# Main.net
KiCad netlist of a schematic drawn in Altium Designer
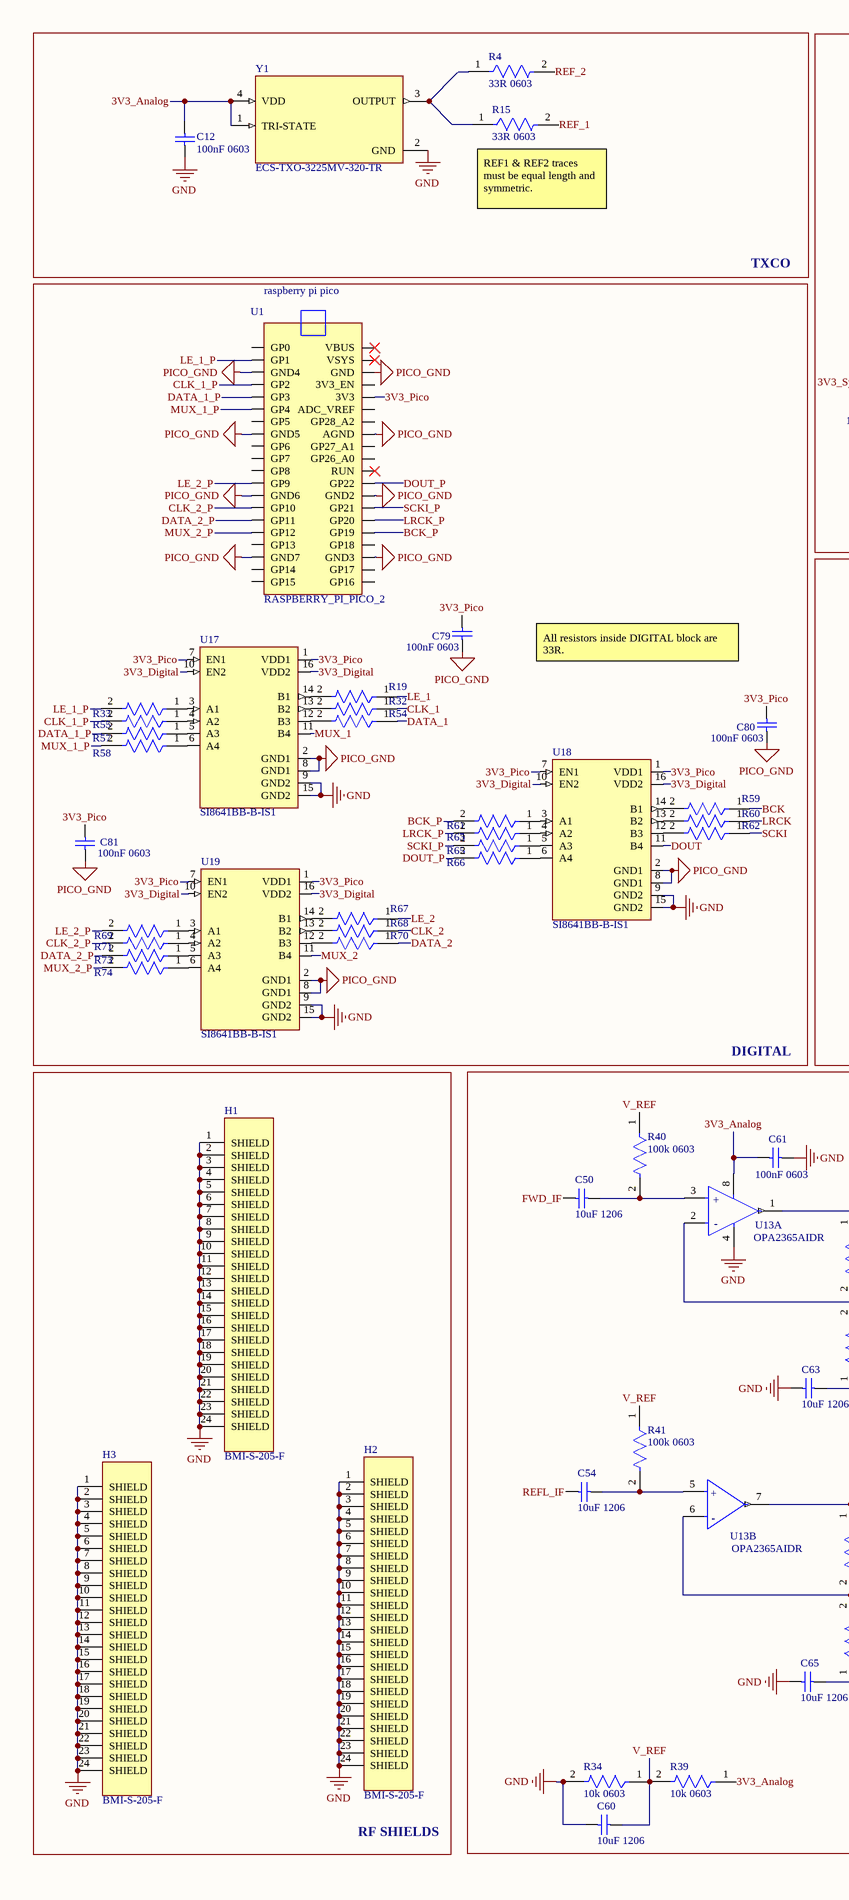
[diagram p0: Main.SchDoc, left]
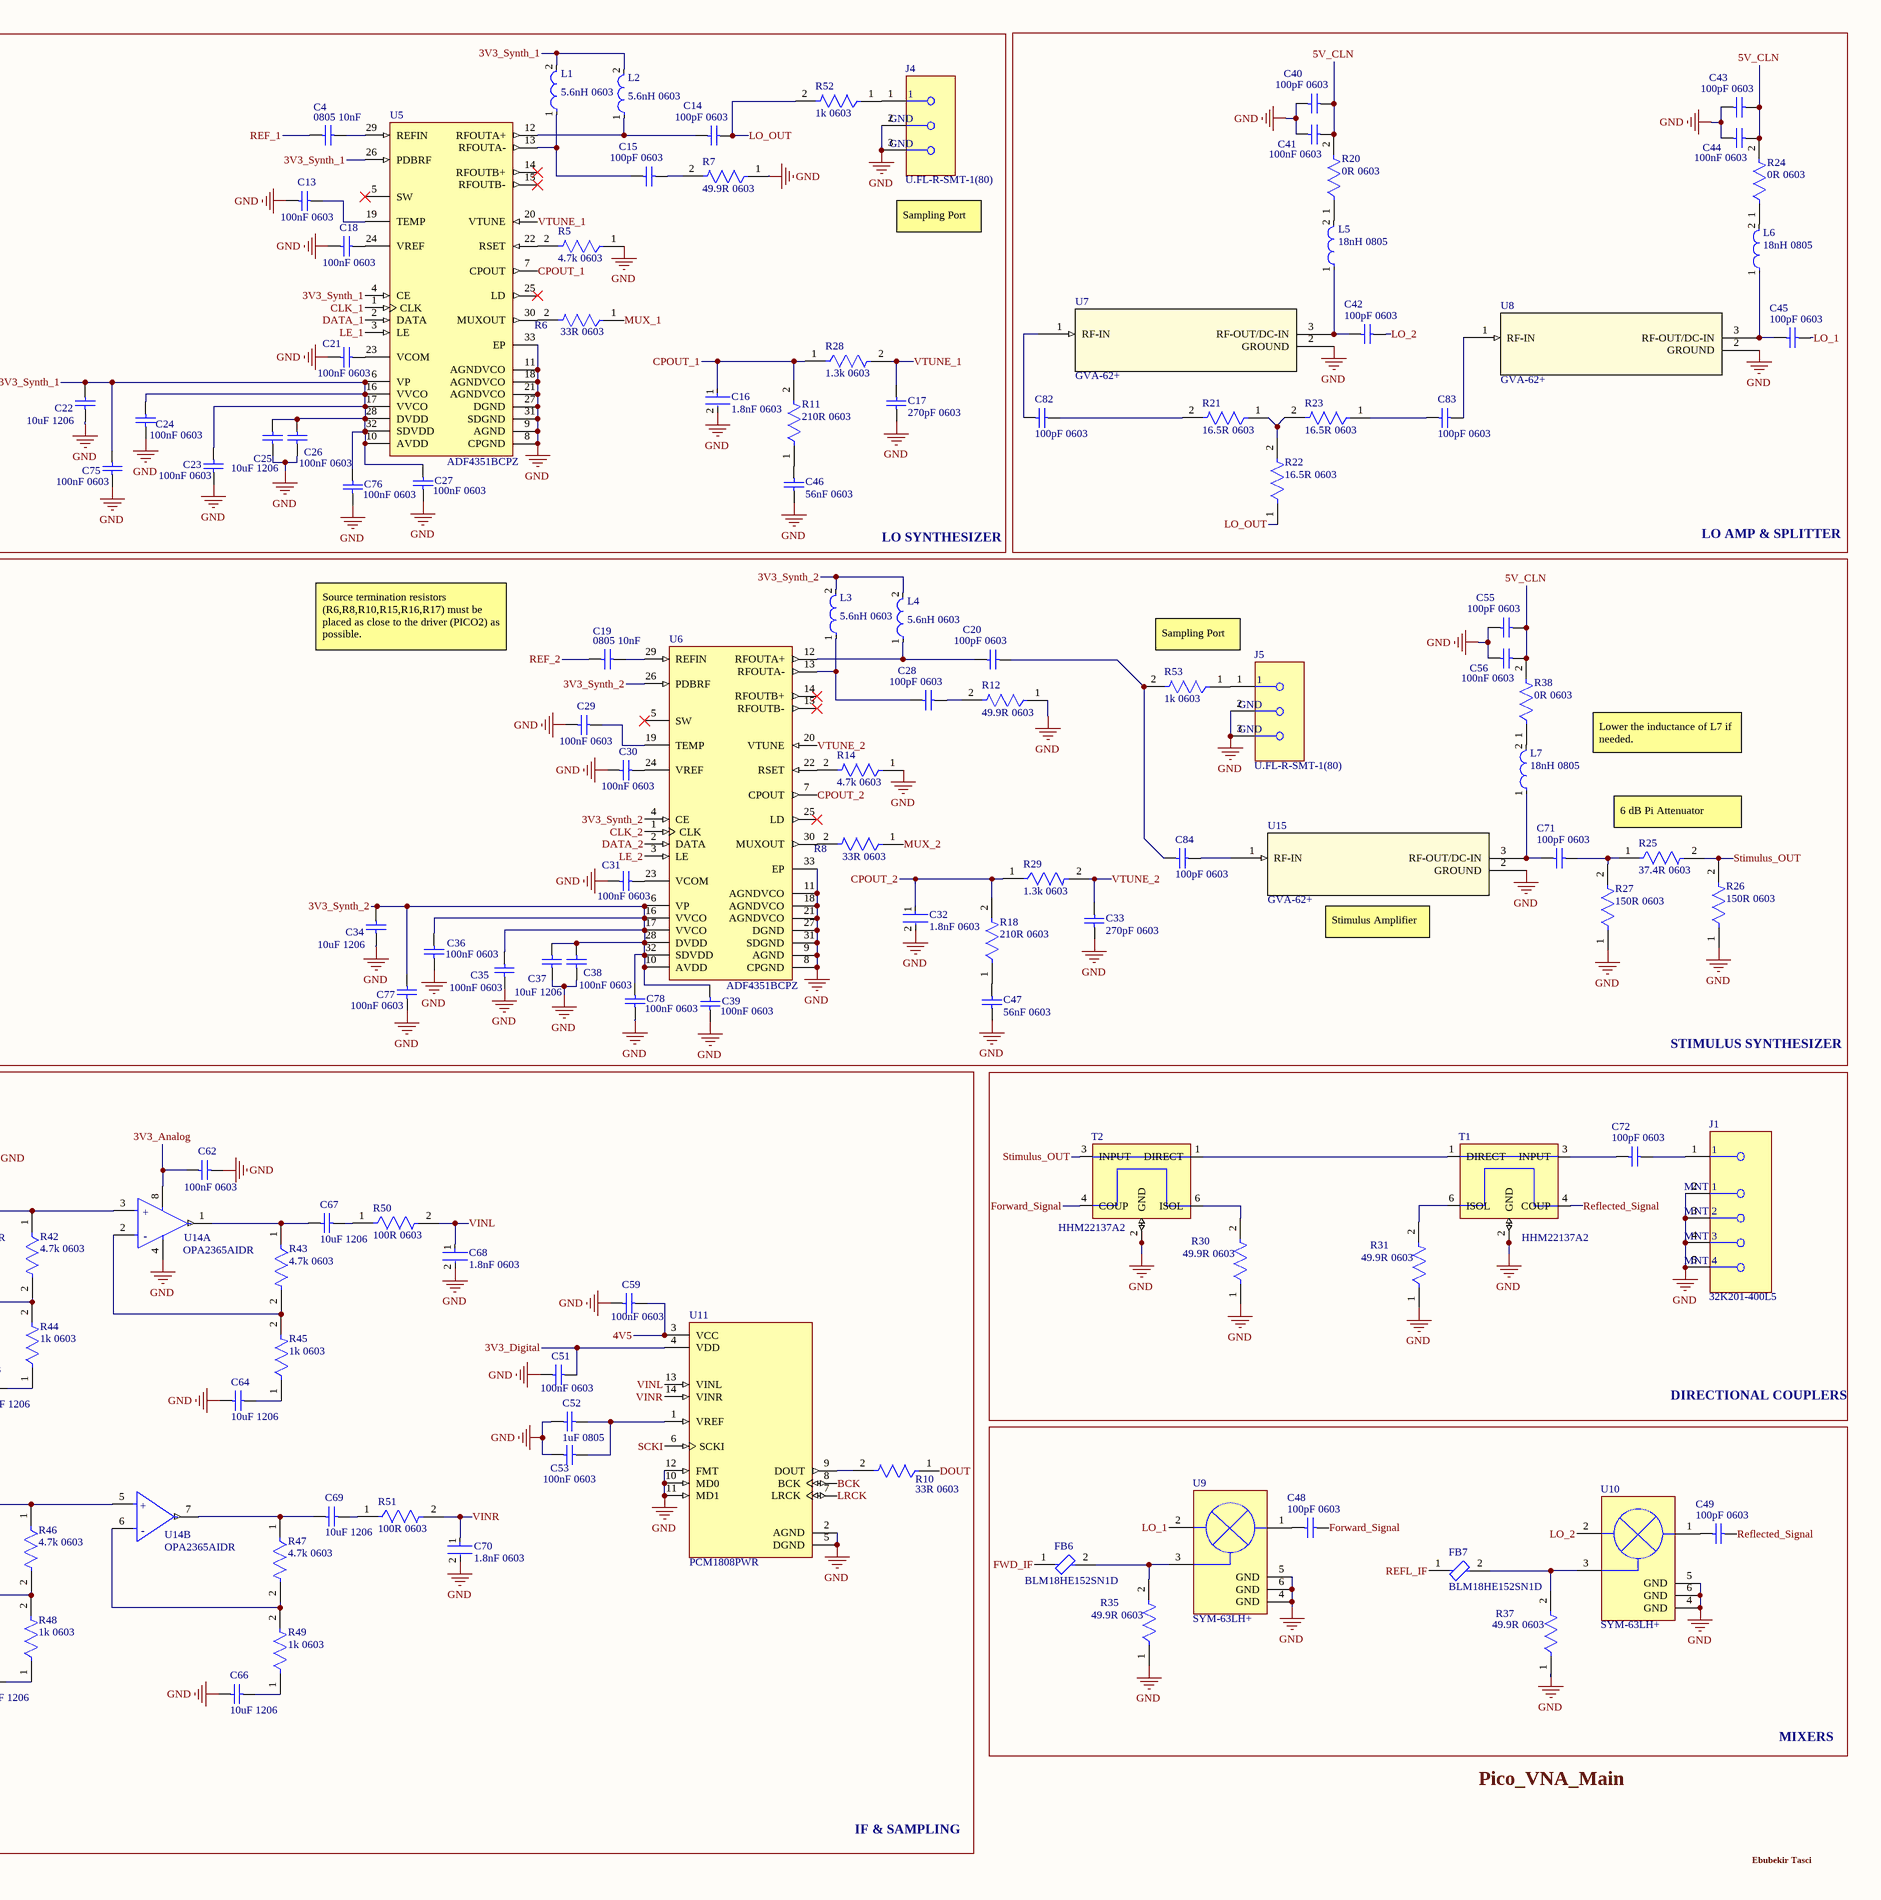
[diagram p1: Main.SchDoc, right]

(export (version "E")
  (design (tool "Eeschema 10.0.6"))
  (components
    (comp (ref "C4")
      (value "0805 10nF")
      (footprint "CAPC2013X94X50ML20T25")
      (fields
        (field (name "MANUFACTURER") "AVX Interconnect / Elco")
        (field (name "PART NUMBER") "0805YC103MAT2A")
      )
      (libsource (lib "Altium Content Vault") (part "CAP"))
    )
    (comp (ref "C12")
      (value "100nF 0603")
      (footprint "CAPC0603(1608)100_N")
      (description "CAP 100nF 25V ±20% 0603 (1608 Metric) Thickness 1mm SMD")
      (fields (field (name "TOLERANCE") "Â±20%"))
      (libsource (lib "Altium Content Vault") (part "CAP"))
    )
    (comp (ref "C13")
      (value "100nF 0603")
      (footprint "CAPC0603(1608)100_N")
      (description "CAP 100nF 25V ±20% 0603 (1608 Metric) Thickness 1mm SMD")
      (fields (field (name "TOLERANCE") "Â±20%"))
      (libsource (lib "Altium Content Vault") (part "CAP"))
    )
    (comp (ref "C14")
      (value "100pF 0603")
      (footprint "CAPC1608X92X38LL15T08")
      (fields (field (name "MANUFACTURER") "Vitramon") (field (name "PART NUMBER") "VJ0603A101FXAAC"))
      (libsource (lib "Altium Content Vault") (part "CAP"))
    )
    (comp (ref "C15")
      (value "100pF 0603")
      (footprint "CAPC1608X92X38LL15T08")
      (fields (field (name "MANUFACTURER") "Vitramon") (field (name "PART NUMBER") "VJ0603A101FXAAC"))
      (libsource (lib "Altium Content Vault") (part "CAP"))
    )
    (comp (ref "C16")
      (value "1.8nF 0603")
      (footprint "FP-C0603C-CF-MFG")
      (description "CAP CER 1800PF 25V X7R 0603")
      (fields (field (name "MANUFACTURER PART NUMBER") "C0603C182J3RACTU") (field (name "TOLERANCE") "0.05"))
      (libsource (lib "Altium Content Vault") (part "b4654b650e69147ec39a6b967a45e02"))
    )
    (comp (ref "C17")
      (value "270pF 0603")
      (footprint "CAPC1608X92X38LL15T08")
      (fields (field (name "PART NUMBER") "VJ0603A271KXAAC") (field (name "MANUFACTURER") "Vitramon"))
      (libsource (lib "Altium Content Vault") (part "CAP"))
    )
    (comp (ref "C18")
      (value "100nF 0603")
      (footprint "CAPC0603(1608)100_N")
      (description "CAP 100nF 25V ±20% 0603 (1608 Metric) Thickness 1mm SMD")
      (fields (field (name "TOLERANCE") "Â±20%"))
      (libsource (lib "Altium Content Vault") (part "CAP"))
    )
    (comp (ref "C19")
      (value "0805 10nF")
      (footprint "CAPC2013X94X50ML20T25")
      (fields
        (field (name "MANUFACTURER") "AVX Interconnect / Elco")
        (field (name "PART NUMBER") "0805YC103MAT2A")
      )
      (libsource (lib "Altium Content Vault") (part "CAP"))
    )
    (comp (ref "C20")
      (value "100pF 0603")
      (footprint "CAPC1608X92X38LL15T08")
      (fields (field (name "MANUFACTURER") "Vitramon") (field (name "PART NUMBER") "VJ0603A101FXAAC"))
      (libsource (lib "Altium Content Vault") (part "CAP"))
    )
    (comp (ref "C21")
      (value "100nF 0603")
      (footprint "CAPC0603(1608)100_N")
      (description "CAP 100nF 25V ±20% 0603 (1608 Metric) Thickness 1mm SMD")
      (fields (field (name "TOLERANCE") "Â±20%"))
      (libsource (lib "Altium Content Vault") (part "CAP"))
    )
    (comp (ref "C22")
      (value "10uF 1206")
      (footprint "CAPC1206(3216)190_M")
      (description "CAP 10uF 16V ±5% 1206 (3216 Metric) Thickness 1.9mm SMD")
      (fields (field (name "TOLERANCE") "Â±5%"))
      (libsource (lib "Altium Content Vault") (part "CAP"))
    )
    (comp (ref "C23")
      (value "100nF 0603")
      (footprint "CAPC0603(1608)100_N")
      (description "CAP 100nF 25V ±20% 0603 (1608 Metric) Thickness 1mm SMD")
      (fields (field (name "TOLERANCE") "Â±20%"))
      (libsource (lib "Altium Content Vault") (part "CAP"))
    )
    (comp (ref "C24")
      (value "100nF 0603")
      (footprint "CAPC0603(1608)100_N")
      (description "CAP 100nF 25V ±20% 0603 (1608 Metric) Thickness 1mm SMD")
      (fields (field (name "TOLERANCE") "Â±20%"))
      (libsource (lib "Altium Content Vault") (part "CAP"))
    )
    (comp (ref "C25")
      (value "10uF 1206")
      (footprint "CAPC1206(3216)190_M")
      (description "CAP 10uF 16V ±5% 1206 (3216 Metric) Thickness 1.9mm SMD")
      (fields (field (name "TOLERANCE") "Â±5%"))
      (libsource (lib "Altium Content Vault") (part "CAP"))
    )
    (comp (ref "C26")
      (value "100nF 0603")
      (footprint "CAPC0603(1608)100_L")
      (description "CAP 100nF 16V ±0.1pF 0603 (1608 Metric) Thickness 1mm SMD")
      (fields (field (name "TOLERANCE") "Â±0.1pF"))
      (libsource (lib "Altium Content Vault") (part "CAP"))
    )
    (comp (ref "C27")
      (value "100nF 0603")
      (footprint "CAPC0603(1608)100_L")
      (description "CAP 100nF 16V ±0.1pF 0603 (1608 Metric) Thickness 1mm SMD")
      (fields (field (name "TOLERANCE") "Â±0.1pF"))
      (libsource (lib "Altium Content Vault") (part "CAP"))
    )
    (comp (ref "C28")
      (value "100pF 0603")
      (footprint "CAPC1608X92X38LL15T08")
      (fields (field (name "MANUFACTURER") "Vitramon") (field (name "PART NUMBER") "VJ0603A101FXAAC"))
      (libsource (lib "Altium Content Vault") (part "CAP"))
    )
    (comp (ref "C29")
      (value "100nF 0603")
      (footprint "CAPC0603(1608)100_N")
      (description "CAP 100nF 25V ±20% 0603 (1608 Metric) Thickness 1mm SMD")
      (fields (field (name "TOLERANCE") "Â±20%"))
      (libsource (lib "Altium Content Vault") (part "CAP"))
    )
    (comp (ref "C30")
      (value "100nF 0603")
      (footprint "CAPC0603(1608)100_N")
      (description "CAP 100nF 25V ±20% 0603 (1608 Metric) Thickness 1mm SMD")
      (fields (field (name "TOLERANCE") "Â±20%"))
      (libsource (lib "Altium Content Vault") (part "CAP"))
    )
    (comp (ref "C31")
      (value "100nF 0603")
      (footprint "CAPC0603(1608)100_N")
      (description "CAP 100nF 25V ±20% 0603 (1608 Metric) Thickness 1mm SMD")
      (fields (field (name "TOLERANCE") "Â±20%"))
      (libsource (lib "Altium Content Vault") (part "CAP"))
    )
    (comp (ref "C32")
      (value "1.8nF 0603")
      (footprint "FP-C0603C-CF-MFG")
      (description "CAP CER 1800PF 25V X7R 0603")
      (fields (field (name "MANUFACTURER PART NUMBER") "C0603C182J3RACTU") (field (name "TOLERANCE") "0.05"))
      (libsource (lib "Altium Content Vault") (part "b4654b650e69147ec39a6b967a45e02"))
    )
    (comp (ref "C33")
      (value "270pF 0603")
      (footprint "CAPC1608X92X38LL15T08")
      (fields (field (name "PART NUMBER") "VJ0603A271KXAAC") (field (name "MANUFACTURER") "Vitramon"))
      (libsource (lib "Altium Content Vault") (part "CAP"))
    )
    (comp (ref "C34")
      (value "10uF 1206")
      (footprint "CAPC1206(3216)190_M")
      (description "CAP 10uF 16V ±5% 1206 (3216 Metric) Thickness 1.9mm SMD")
      (fields (field (name "TOLERANCE") "Â±5%"))
      (libsource (lib "Altium Content Vault") (part "CAP"))
    )
    (comp (ref "C35")
      (value "100nF 0603")
      (footprint "CAPC0603(1608)100_N")
      (description "CAP 100nF 25V ±20% 0603 (1608 Metric) Thickness 1mm SMD")
      (fields (field (name "TOLERANCE") "Â±20%"))
      (libsource (lib "Altium Content Vault") (part "CAP"))
    )
    (comp (ref "C36")
      (value "100nF 0603")
      (footprint "CAPC0603(1608)100_N")
      (description "CAP 100nF 25V ±20% 0603 (1608 Metric) Thickness 1mm SMD")
      (fields (field (name "TOLERANCE") "Â±20%"))
      (libsource (lib "Altium Content Vault") (part "CAP"))
    )
    (comp (ref "C37")
      (value "10uF 1206")
      (footprint "CAPC1206(3216)190_M")
      (description "CAP 10uF 16V ±5% 1206 (3216 Metric) Thickness 1.9mm SMD")
      (fields (field (name "TOLERANCE") "Â±5%"))
      (libsource (lib "Altium Content Vault") (part "CAP"))
    )
    (comp (ref "C38")
      (value "100nF 0603")
      (footprint "CAPC0603(1608)100_L")
      (description "CAP 100nF 16V ±0.1pF 0603 (1608 Metric) Thickness 1mm SMD")
      (fields (field (name "TOLERANCE") "Â±0.1pF"))
      (libsource (lib "Altium Content Vault") (part "CAP"))
    )
    (comp (ref "C39")
      (value "100nF 0603")
      (footprint "CAPC0603(1608)100_L")
      (description "CAP 100nF 16V ±0.1pF 0603 (1608 Metric) Thickness 1mm SMD")
      (fields (field (name "TOLERANCE") "Â±0.1pF"))
      (libsource (lib "Altium Content Vault") (part "CAP"))
    )
    (comp (ref "C40")
      (value "100pF 0603")
      (footprint "CAPC1608X92X38LL15T08")
      (fields (field (name "MANUFACTURER") "Vitramon") (field (name "PART NUMBER") "VJ0603A101FXAAC"))
      (libsource (lib "Altium Content Vault") (part "CAP"))
    )
    (comp (ref "C41")
      (value "100nF 0603")
      (footprint "CAPC0603(1608)100_N")
      (description "CAP 100nF 25V ±20% 0603 (1608 Metric) Thickness 1mm SMD")
      (fields (field (name "TOLERANCE") "Â±20%"))
      (libsource (lib "Altium Content Vault") (part "CAP"))
    )
    (comp (ref "C42")
      (value "100pF 0603")
      (footprint "CAPC1608X92X38LL15T08")
      (fields (field (name "MANUFACTURER") "Vitramon") (field (name "PART NUMBER") "VJ0603A101FXAAC"))
      (libsource (lib "Altium Content Vault") (part "CAP"))
    )
    (comp (ref "C43")
      (value "100pF 0603")
      (footprint "CAPC1608X92X38LL15T08")
      (fields (field (name "MANUFACTURER") "Vitramon") (field (name "PART NUMBER") "VJ0603A101FXAAC"))
      (libsource (lib "Altium Content Vault") (part "CAP"))
    )
    (comp (ref "C44")
      (value "100nF 0603")
      (footprint "CAPC0603(1608)100_N")
      (description "CAP 100nF 25V ±20% 0603 (1608 Metric) Thickness 1mm SMD")
      (fields (field (name "TOLERANCE") "Â±20%"))
      (libsource (lib "Altium Content Vault") (part "CAP"))
    )
    (comp (ref "C45")
      (value "100pF 0603")
      (footprint "CAPC1608X92X38LL15T08")
      (fields (field (name "MANUFACTURER") "Vitramon") (field (name "PART NUMBER") "VJ0603A101FXAAC"))
      (libsource (lib "Altium Content Vault") (part "CAP"))
    )
    (comp (ref "C46")
      (value "56nF 0603")
      (footprint "CAPC1608X90X35LL15T15")
      (fields
        (field (name "PART NUMBER") "0603YC563JAT2A")
        (field (name "MANUFACTURER") "AVX Interconnect / Elco")
      )
      (libsource (lib "Altium Content Vault") (part "CAP"))
    )
    (comp (ref "C47")
      (value "56nF 0603")
      (footprint "CAPC1608X90X35LL15T15")
      (fields
        (field (name "PART NUMBER") "0603YC563JAT2A")
        (field (name "MANUFACTURER") "AVX Interconnect / Elco")
      )
      (libsource (lib "Altium Content Vault") (part "CAP"))
    )
    (comp (ref "C48")
      (value "100pF 0603")
      (footprint "CAPC1608X92X38LL15T08")
      (fields (field (name "MANUFACTURER") "Vitramon") (field (name "PART NUMBER") "VJ0603A101FXAAC"))
      (libsource (lib "Altium Content Vault") (part "CAP"))
    )
    (comp (ref "C49")
      (value "100pF 0603")
      (footprint "CAPC1608X92X38LL15T08")
      (fields (field (name "MANUFACTURER") "Vitramon") (field (name "PART NUMBER") "VJ0603A101FXAAC"))
      (libsource (lib "Altium Content Vault") (part "CAP"))
    )
    (comp (ref "C50")
      (value "10uF 1206")
      (footprint "CAPC1206(3216)190_M")
      (description "CAP 10uF 16V ±5% 1206 (3216 Metric) Thickness 1.9mm SMD")
      (fields (field (name "TOLERANCE") "Â±5%"))
      (libsource (lib "Altium Content Vault") (part "CAP"))
    )
    (comp (ref "C51")
      (value "100nF 0603")
      (footprint "CAPC0603(1608)100_N")
      (description "CAP 100nF 25V ±20% 0603 (1608 Metric) Thickness 1mm SMD")
      (fields (field (name "TOLERANCE") "Â±20%"))
      (libsource (lib "Altium Content Vault") (part "CAP"))
    )
    (comp (ref "C52")
      (value "1uF 0805")
      (footprint "CAPC2013X145X50NL20T25")
      (fields (field (name "PART NUMBER") "C0805C105J3RACTU") (field (name "MANUFACTURER") "Kemet"))
      (libsource (lib "Altium Content Vault") (part "CAP"))
    )
    (comp (ref "C53")
      (value "100nF 0603")
      (footprint "CAPC0603(1608)100_N")
      (description "CAP 100nF 25V ±20% 0603 (1608 Metric) Thickness 1mm SMD")
      (fields (field (name "TOLERANCE") "Â±20%"))
      (libsource (lib "Altium Content Vault") (part "CAP"))
    )
    (comp (ref "C54")
      (value "10uF 1206")
      (footprint "CAPC1206(3216)190_M")
      (description "CAP 10uF 16V ±5% 1206 (3216 Metric) Thickness 1.9mm SMD")
      (fields (field (name "TOLERANCE") "Â±5%"))
      (libsource (lib "Altium Content Vault") (part "CAP"))
    )
    (comp (ref "C55")
      (value "100pF 0603")
      (footprint "CAPC1608X92X38LL15T08")
      (fields (field (name "MANUFACTURER") "Vitramon") (field (name "PART NUMBER") "VJ0603A101FXAAC"))
      (libsource (lib "Altium Content Vault") (part "CAP"))
    )
    (comp (ref "C56")
      (value "100nF 0603")
      (footprint "CAPC0603(1608)100_N")
      (description "CAP 100nF 25V ±20% 0603 (1608 Metric) Thickness 1mm SMD")
      (fields (field (name "TOLERANCE") "Â±20%"))
      (libsource (lib "Altium Content Vault") (part "CAP"))
    )
    (comp (ref "C59")
      (value "100nF 0603")
      (footprint "CAPC0603(1608)100_N")
      (description "CAP 100nF 25V ±20% 0603 (1608 Metric) Thickness 1mm SMD")
      (fields (field (name "TOLERANCE") "Â±20%"))
      (libsource (lib "Altium Content Vault") (part "CAP"))
    )
    (comp (ref "C60")
      (value "10uF 1206")
      (footprint "CAPC1206(3216)190_M")
      (description "CAP 10uF 16V ±5% 1206 (3216 Metric) Thickness 1.9mm SMD")
      (fields (field (name "TOLERANCE") "Â±5%"))
      (libsource (lib "Altium Content Vault") (part "CAP"))
    )
    (comp (ref "C61")
      (value "100nF 0603")
      (footprint "CAPC0603(1608)100_N")
      (description "CAP 100nF 25V ±20% 0603 (1608 Metric) Thickness 1mm SMD")
      (fields (field (name "TOLERANCE") "Â±20%"))
      (libsource (lib "Altium Content Vault") (part "CAP"))
    )
    (comp (ref "C62")
      (value "100nF 0603")
      (footprint "CAPC0603(1608)100_N")
      (description "CAP 100nF 25V ±20% 0603 (1608 Metric) Thickness 1mm SMD")
      (fields (field (name "TOLERANCE") "Â±20%"))
      (libsource (lib "Altium Content Vault") (part "CAP"))
    )
    (comp (ref "C63")
      (value "10uF 1206")
      (footprint "CAPC1206(3216)190_M")
      (description "CAP 10uF 16V ±5% 1206 (3216 Metric) Thickness 1.9mm SMD")
      (fields (field (name "TOLERANCE") "Â±5%"))
      (libsource (lib "Altium Content Vault") (part "CAP"))
    )
    (comp (ref "C64")
      (value "10uF 1206")
      (footprint "CAPC1206(3216)190_M")
      (description "CAP 10uF 16V ±5% 1206 (3216 Metric) Thickness 1.9mm SMD")
      (fields (field (name "TOLERANCE") "Â±5%"))
      (libsource (lib "Altium Content Vault") (part "CAP"))
    )
    (comp (ref "C65")
      (value "10uF 1206")
      (footprint "CAPC1206(3216)190_M")
      (description "CAP 10uF 16V ±5% 1206 (3216 Metric) Thickness 1.9mm SMD")
      (fields (field (name "TOLERANCE") "Â±5%"))
      (libsource (lib "Altium Content Vault") (part "CAP"))
    )
    (comp (ref "C66")
      (value "10uF 1206")
      (footprint "CAPC1206(3216)190_M")
      (description "CAP 10uF 16V ±5% 1206 (3216 Metric) Thickness 1.9mm SMD")
      (fields (field (name "TOLERANCE") "Â±5%"))
      (libsource (lib "Altium Content Vault") (part "CAP"))
    )
    (comp (ref "C67")
      (value "10uF 1206")
      (footprint "CAPC1206(3216)190_M")
      (description "CAP 10uF 16V ±5% 1206 (3216 Metric) Thickness 1.9mm SMD")
      (fields (field (name "TOLERANCE") "Â±5%"))
      (libsource (lib "Altium Content Vault") (part "CAP"))
    )
    (comp (ref "C68")
      (value "1.8nF 0603")
      (footprint "FP-C0603C-CF-MFG")
      (description "CAP CER 1800PF 25V X7R 0603")
      (fields (field (name "MANUFACTURER PART NUMBER") "C0603C182J3RACTU") (field (name "TOLERANCE") "0.05"))
      (libsource (lib "Altium Content Vault") (part "b4654b650e69147ec39a6b967a45e02"))
    )
    (comp (ref "C69")
      (value "10uF 1206")
      (footprint "CAPC1206(3216)190_M")
      (description "CAP 10uF 16V ±5% 1206 (3216 Metric) Thickness 1.9mm SMD")
      (fields (field (name "TOLERANCE") "Â±5%"))
      (libsource (lib "Altium Content Vault") (part "CAP"))
    )
    (comp (ref "C70")
      (value "1.8nF 0603")
      (footprint "FP-C0603C-CF-MFG")
      (description "CAP CER 1800PF 25V X7R 0603")
      (fields (field (name "MANUFACTURER PART NUMBER") "C0603C182J3RACTU") (field (name "TOLERANCE") "0.05"))
      (libsource (lib "Altium Content Vault") (part "b4654b650e69147ec39a6b967a45e02"))
    )
    (comp (ref "C71")
      (value "100pF 0603")
      (footprint "CAPC1608X92X38LL15T08")
      (fields (field (name "MANUFACTURER") "Vitramon") (field (name "PART NUMBER") "VJ0603A101FXAAC"))
      (libsource (lib "Altium Content Vault") (part "CAP"))
    )
    (comp (ref "C72")
      (value "100pF 0603")
      (footprint "CAPC1608X92X38LL15T08")
      (fields (field (name "MANUFACTURER") "Vitramon") (field (name "PART NUMBER") "VJ0603A101FXAAC"))
      (libsource (lib "Altium Content Vault") (part "CAP"))
    )
    (comp (ref "C75")
      (value "100nF 0603")
      (footprint "CAPC0603(1608)100_N")
      (description "CAP 100nF 25V ±20% 0603 (1608 Metric) Thickness 1mm SMD")
      (fields (field (name "TOLERANCE") "Â±20%"))
      (libsource (lib "Altium Content Vault") (part "CAP"))
    )
    (comp (ref "C76")
      (value "100nF 0603")
      (footprint "CAPC0603(1608)100_L")
      (description "CAP 100nF 16V ±0.1pF 0603 (1608 Metric) Thickness 1mm SMD")
      (fields (field (name "TOLERANCE") "Â±0.1pF"))
      (libsource (lib "Altium Content Vault") (part "CAP"))
    )
    (comp (ref "C77")
      (value "100nF 0603")
      (footprint "CAPC0603(1608)100_N")
      (description "CAP 100nF 25V ±20% 0603 (1608 Metric) Thickness 1mm SMD")
      (fields (field (name "TOLERANCE") "Â±20%"))
      (libsource (lib "Altium Content Vault") (part "CAP"))
    )
    (comp (ref "C78")
      (value "100nF 0603")
      (footprint "CAPC0603(1608)100_L")
      (description "CAP 100nF 16V ±0.1pF 0603 (1608 Metric) Thickness 1mm SMD")
      (fields (field (name "TOLERANCE") "Â±0.1pF"))
      (libsource (lib "Altium Content Vault") (part "CAP"))
    )
    (comp (ref "C79")
      (value "100nF 0603")
      (footprint "CAPC0603(1608)100_N")
      (description "CAP 100nF 25V ±20% 0603 (1608 Metric) Thickness 1mm SMD")
      (fields (field (name "TOLERANCE") "Â±20%"))
      (libsource (lib "Altium Content Vault") (part "CAP"))
    )
    (comp (ref "C80")
      (value "100nF 0603")
      (footprint "CAPC0603(1608)100_N")
      (description "CAP 100nF 25V ±20% 0603 (1608 Metric) Thickness 1mm SMD")
      (fields (field (name "TOLERANCE") "Â±20%"))
      (libsource (lib "Altium Content Vault") (part "CAP"))
    )
    (comp (ref "C81")
      (value "100nF 0603")
      (footprint "CAPC0603(1608)100_N")
      (description "CAP 100nF 25V ±20% 0603 (1608 Metric) Thickness 1mm SMD")
      (fields (field (name "TOLERANCE") "Â±20%"))
      (libsource (lib "Altium Content Vault") (part "CAP"))
    )
    (comp (ref "C82")
      (value "100pF 0603")
      (footprint "CAPC1608X92X38LL15T08")
      (fields (field (name "MANUFACTURER") "Vitramon") (field (name "PART NUMBER") "VJ0603A101FXAAC"))
      (libsource (lib "Altium Content Vault") (part "CAP"))
    )
    (comp (ref "C83")
      (value "100pF 0603")
      (footprint "CAPC1608X92X38LL15T08")
      (fields (field (name "MANUFACTURER") "Vitramon") (field (name "PART NUMBER") "VJ0603A101FXAAC"))
      (libsource (lib "Altium Content Vault") (part "CAP"))
    )
    (comp (ref "C84")
      (value "100pF 0603")
      (footprint "CAPC1608X92X38LL15T08")
      (fields (field (name "MANUFACTURER") "Vitramon") (field (name "PART NUMBER") "VJ0603A101FXAAC"))
      (libsource (lib "Altium Content Vault") (part "CAP"))
    )
    (comp (ref "FB6")
      (value "BLM18HE152SN1D")
      (footprint "FP-BLM18-0_15-t0_8-IPC_C")
      (description "Chip Ferrite Bead, 0603, 1500Ω @ 100MHz, 0.5Ω, 25%, 500mA")
      (fields (field (name "TOLERANCE") "25%"))
      (libsource (lib "Altium Content Vault") (part "5f30dd21d616792df468990f7003faa"))
    )
    (comp (ref "FB7")
      (value "BLM18HE152SN1D")
      (footprint "FP-BLM18-0_15-t0_8-IPC_C")
      (description "Chip Ferrite Bead, 0603, 1500Ω @ 100MHz, 0.5Ω, 25%, 500mA")
      (fields (field (name "TOLERANCE") "25%"))
      (libsource (lib "Altium Content Vault") (part "5f30dd21d616792df468990f7003faa"))
    )
    (comp (ref "H1")
      (value "BMI-S-205-F")
      (footprint "LAIRD_BMI-S-205-F")
      (description "RF Shield Frame 1.000 _25.40mm_ X 1.500 _38.10mm_ Solder")
      (fields (field (name "MF") "Laird Technologies"))
      (libsource (lib "Ebubekir Taşcı") (part "BMI-S-205-F"))
    )
    (comp (ref "H2")
      (value "BMI-S-205-F")
      (footprint "LAIRD_BMI-S-205-F")
      (description "RF Shield Frame 1.000 _25.40mm_ X 1.500 _38.10mm_ Solder")
      (fields (field (name "MF") "Laird Technologies"))
      (libsource (lib "Ebubekir Taşcı") (part "BMI-S-205-F"))
    )
    (comp (ref "H3")
      (value "BMI-S-205-F")
      (footprint "LAIRD_BMI-S-205-F")
      (description "RF Shield Frame 1.000 _25.40mm_ X 1.500 _38.10mm_ Solder")
      (fields (field (name "MF") "Laird Technologies"))
      (libsource (lib "Ebubekir Taşcı") (part "BMI-S-205-F"))
    )
    (comp (ref "J1")
      (value "32K201-400L5")
      (footprint "FP-32K201-400L5-MFG")
      (description "CONN SMA JACK R/A 50OHM PCB")
      (libsource (lib "Altium Content Vault") (part "42d0677c2d2b90080c021db52569f63"))
    )
    (comp (ref "J4")
      (value "U.FL-R-SMT-1(80)")
      (footprint "FP-U_FL-R-SMT-1_80-MFG")
      (description "CONN U.FL RCPT STR 50 OHM SMD")
      (libsource (lib "Altium Content Vault") (part "ad010367dc7cd7c7a13299a56582dd6"))
    )
    (comp (ref "J5")
      (value "U.FL-R-SMT-1(80)")
      (footprint "FP-U_FL-R-SMT-1_80-MFG")
      (description "CONN U.FL RCPT STR 50 OHM SMD")
      (libsource (lib "Altium Content Vault") (part "ad010367dc7cd7c7a13299a56582dd6"))
    )
    (comp (ref "L1")
      (value "5.6nH 0603")
      (footprint "FP-AISC-0603HP-MFG")
      (libsource (lib "Altium Content Vault") (part "725321dda6339637d4d059423bc1c3c"))
    )
    (comp (ref "L2")
      (value "5.6nH 0603")
      (footprint "FP-AISC-0603HP-MFG")
      (libsource (lib "Altium Content Vault") (part "725321dda6339637d4d059423bc1c3c"))
    )
    (comp (ref "L3")
      (value "5.6nH 0603")
      (footprint "FP-AISC-0603HP-MFG")
      (libsource (lib "Altium Content Vault") (part "725321dda6339637d4d059423bc1c3c"))
    )
    (comp (ref "L4")
      (value "5.6nH 0603")
      (footprint "FP-AISC-0603HP-MFG")
      (libsource (lib "Altium Content Vault") (part "725321dda6339637d4d059423bc1c3c"))
    )
    (comp (ref "L5")
      (value "18nH 0805")
      (footprint "FP-LQW2BAN_00-MFG")
      (description "18 nH Unshielded Drum Core, Wirewound Inductor 800 mA 130mOhm 0805 (2012 Metric)\r\n0805CT-180EGTS")
      (fields (field (name "TOLERANCE") "5%"))
      (libsource (lib "Altium Content Vault") (part "725321dda6339637d4d059423bc1c3c"))
    )
    (comp (ref "L6")
      (value "18nH 0805")
      (footprint "FP-LQW2BAN_00-MFG")
      (description "18 nH Unshielded Drum Core, Wirewound Inductor 800 mA 130mOhm 0805 (2012 Metric)\r\n0805CT-180EGTS")
      (fields (field (name "TOLERANCE") "5%"))
      (libsource (lib "Altium Content Vault") (part "725321dda6339637d4d059423bc1c3c"))
    )
    (comp (ref "L7")
      (value "18nH 0805")
      (footprint "FP-LQW2BAN_00-MFG")
      (description "18 nH Unshielded Drum Core, Wirewound Inductor 800 mA 130mOhm 0805 (2012 Metric)\r\n0805CT-180EGTS")
      (fields (field (name "TOLERANCE") "5%"))
      (libsource (lib "Altium Content Vault") (part "725321dda6339637d4d059423bc1c3c"))
    )
    (comp (ref "R4")
      (value "33R 0603")
      (footprint "FP-SR0603-MFG")
      (description "RES 33 OHM 1% 1/4W 0603")
      (fields
        (field (name "MANUFACTURER") "Yageo")
        (field (name "MANUFACTURER PART NUMBER") "SR0603FR-7T33RL")
      )
      (libsource (lib "Altium Content Vault") (part "1029c3af85768c4190bb7ad29bc67b5"))
    )
    (comp (ref "R5")
      (value "4.7k 0603")
      (footprint "FP-CPF0603-MFG")
      (description "RES SMD 4.7kΩ 0.1% 1/16W 0603")
      (fields (field (name "TOLERANCE") "0.1%") (field (name "MANUFACTURER") "TE Connectivity"))
      (libsource (lib "Altium Content Vault") (part "1029c3af85768c4190bb7ad29bc67b5"))
    )
    (comp (ref "R6")
      (value "33R 0603")
      (footprint "FP-CPF0603-MFG")
      (description "RES SMD 33Ω 0.1% 1/16W 0603")
      (fields
        (field (name "OCTOPART") "https://octopart.com/cpf0603b430re1-te+connectivity-22738753")
        (field (name "MANUFACTURER PART NUMBER") "CPF0603B430RE1")
      )
      (libsource (lib "Altium Content Vault") (part "1029c3af85768c4190bb7ad29bc67b5"))
    )
    (comp (ref "R7")
      (value "49.9R 0603")
      (footprint "FP-RT0603-MFG")
      (description "RES SMD 49.9 OHM 1% 1/10W 0603")
      (fields (field (name "TOLERANCE") "0.01") (field (name "MANUFACTURER") "Yageo"))
      (libsource (lib "Altium Content Vault") (part "1029c3af85768c4190bb7ad29bc67b5"))
    )
    (comp (ref "R8")
      (value "33R 0603")
      (footprint "FP-CPF0603-MFG")
      (description "RES SMD 33Ω 0.1% 1/16W 0603")
      (fields
        (field (name "OCTOPART") "https://octopart.com/cpf0603b430re1-te+connectivity-22738753")
        (field (name "MANUFACTURER PART NUMBER") "CPF0603B430RE1")
      )
      (libsource (lib "Altium Content Vault") (part "1029c3af85768c4190bb7ad29bc67b5"))
    )
    (comp (ref "R10")
      (value "33R 0603")
      (footprint "FP-CPF0603-MFG")
      (description "RES SMD 33Ω 0.1% 1/16W 0603")
      (fields
        (field (name "OCTOPART") "https://octopart.com/cpf0603b430re1-te+connectivity-22738753")
        (field (name "MANUFACTURER PART NUMBER") "CPF0603B430RE1")
      )
      (libsource (lib "Altium Content Vault") (part "1029c3af85768c4190bb7ad29bc67b5"))
    )
    (comp (ref "R11")
      (value "210R 0603")
      (footprint "FP-AC0603-IPC_B")
      (description "RES 210Ω 1.00% 0.1W 0603")
      (fields (field (name "TOLERANCE") "1%"))
      (libsource (lib "Altium Content Vault") (part "1029c3af85768c4190bb7ad29bc67b5"))
    )
    (comp (ref "R12")
      (value "49.9R 0603")
      (footprint "FP-RT0603-MFG")
      (description "RES SMD 49.9 OHM 1% 1/10W 0603")
      (fields (field (name "TOLERANCE") "0.01") (field (name "MANUFACTURER") "Yageo"))
      (libsource (lib "Altium Content Vault") (part "1029c3af85768c4190bb7ad29bc67b5"))
    )
    (comp (ref "R14")
      (value "4.7k 0603")
      (footprint "FP-CPF0603-MFG")
      (description "RES SMD 4.7kΩ 0.1% 1/16W 0603")
      (fields (field (name "TOLERANCE") "0.1%") (field (name "MANUFACTURER") "TE Connectivity"))
      (libsource (lib "Altium Content Vault") (part "1029c3af85768c4190bb7ad29bc67b5"))
    )
    (comp (ref "R15")
      (value "33R 0603")
      (footprint "FP-SR0603-MFG")
      (description "RES 33 OHM 1% 1/4W 0603")
      (fields
        (field (name "MANUFACTURER") "Yageo")
        (field (name "MANUFACTURER PART NUMBER") "SR0603FR-7T33RL")
      )
      (libsource (lib "Altium Content Vault") (part "1029c3af85768c4190bb7ad29bc67b5"))
    )
    (comp (ref "R18")
      (value "210R 0603")
      (footprint "FP-AC0603-IPC_B")
      (description "RES 210Ω 1.00% 0.1W 0603")
      (fields (field (name "TOLERANCE") "1%"))
      (libsource (lib "Altium Content Vault") (part "1029c3af85768c4190bb7ad29bc67b5"))
    )
    (comp (ref "R19")
      (value "33R 0603")
      (footprint "FP-CPF0603-MFG")
      (description "RES SMD 33Ω 0.1% 1/16W 0603")
      (fields
        (field (name "OCTOPART") "https://octopart.com/cpf0603b430re1-te+connectivity-22738753")
        (field (name "MANUFACTURER PART NUMBER") "CPF0603B430RE1")
      )
      (libsource (lib "Altium Content Vault") (part "1029c3af85768c4190bb7ad29bc67b5"))
    )
    (comp (ref "R20")
      (value "0R 0603")
      (footprint "FP-HCJ0603-MFG")
      (description "RES 0 OHM JUMPER 1/4W 0603")
      (libsource (lib "Altium Content Vault") (part "1029c3af85768c4190bb7ad29bc67b5"))
    )
    (comp (ref "R21")
      (value "16.5R 0603")
      (footprint "FP-RT0603-MFG")
      (description "RES SMD 16.5 OHM 1% 1/10W 0603")
      (fields (field (name "MANUFACTURER PART NUMBER") "RT0603FRE0716R5L") (field (name "TOLERANCE") "0.01"))
      (libsource (lib "Altium Content Vault") (part "1029c3af85768c4190bb7ad29bc67b5"))
    )
    (comp (ref "R22")
      (value "16.5R 0603")
      (footprint "FP-RT0603-MFG")
      (description "RES SMD 16.5 OHM 1% 1/10W 0603")
      (fields (field (name "MANUFACTURER PART NUMBER") "RT0603FRE0716R5L") (field (name "TOLERANCE") "0.01"))
      (libsource (lib "Altium Content Vault") (part "1029c3af85768c4190bb7ad29bc67b5"))
    )
    (comp (ref "R23")
      (value "16.5R 0603")
      (footprint "FP-RT0603-MFG")
      (description "RES SMD 16.5 OHM 1% 1/10W 0603")
      (fields (field (name "MANUFACTURER PART NUMBER") "RT0603FRE0716R5L") (field (name "TOLERANCE") "0.01"))
      (libsource (lib "Altium Content Vault") (part "1029c3af85768c4190bb7ad29bc67b5"))
    )
    (comp (ref "R24")
      (value "0R 0603")
      (footprint "FP-HCJ0603-MFG")
      (description "RES 0 OHM JUMPER 1/4W 0603")
      (libsource (lib "Altium Content Vault") (part "1029c3af85768c4190bb7ad29bc67b5"))
    )
    (comp (ref "R25")
      (value "37.4R 0603")
      (footprint "FP-RT0603-MFG")
      (description "RES SMD 37.4 OHM 0.1% 1/10W 0603")
      (fields
        (field (name "OCTOPART") "https://octopart.com/rt0603brd0737r4l-yageo-1279906")
        (field (name "MANUFACTURER") "Yageo")
      )
      (libsource (lib "Altium Content Vault") (part "1029c3af85768c4190bb7ad29bc67b5"))
    )
    (comp (ref "R26")
      (value "150R 0603")
      (footprint "FP-RT0603-MFG")
      (description "RES 150 OHM 1/10W .1% SMD 0603")
      (fields
        (field (name "OCTOPART") "https://octopart.com/rt0603bre07150rl-yageo-1267230")
        (field (name "TOLERANCE") "0.001")
      )
      (libsource (lib "Altium Content Vault") (part "1029c3af85768c4190bb7ad29bc67b5"))
    )
    (comp (ref "R27")
      (value "150R 0603")
      (footprint "FP-RT0603-MFG")
      (description "RES 150 OHM 1/10W .1% SMD 0603")
      (fields
        (field (name "OCTOPART") "https://octopart.com/rt0603bre07150rl-yageo-1267230")
        (field (name "TOLERANCE") "0.001")
      )
      (libsource (lib "Altium Content Vault") (part "1029c3af85768c4190bb7ad29bc67b5"))
    )
    (comp (ref "R28")
      (value "1.3k 0603")
      (footprint "FP-TFCR0603-IPC_B")
      (description "RES Thin Film,  1.3kΩ, 0.1%, 0.1W, 25ppm/°C, 0603")
      (libsource (lib "Altium Content Vault") (part "1029c3af85768c4190bb7ad29bc67b5"))
    )
    (comp (ref "R29")
      (value "1.3k 0603")
      (footprint "FP-TFCR0603-IPC_B")
      (description "RES Thin Film,  1.3kΩ, 0.1%, 0.1W, 25ppm/°C, 0603")
      (libsource (lib "Altium Content Vault") (part "1029c3af85768c4190bb7ad29bc67b5"))
    )
    (comp (ref "R30")
      (value "49.9R 0603")
      (footprint "FP-RT0603-MFG")
      (description "RES SMD 49.9 OHM 1% 1/10W 0603")
      (fields (field (name "TOLERANCE") "0.01") (field (name "MANUFACTURER") "Yageo"))
      (libsource (lib "Altium Content Vault") (part "1029c3af85768c4190bb7ad29bc67b5"))
    )
    (comp (ref "R31")
      (value "49.9R 0603")
      (footprint "FP-RT0603-MFG")
      (description "RES SMD 49.9 OHM 1% 1/10W 0603")
      (fields (field (name "TOLERANCE") "0.01") (field (name "MANUFACTURER") "Yageo"))
      (libsource (lib "Altium Content Vault") (part "1029c3af85768c4190bb7ad29bc67b5"))
    )
    (comp (ref "R32")
      (value "33R 0603")
      (footprint "FP-CPF0603-MFG")
      (description "RES SMD 33Ω 0.1% 1/16W 0603")
      (fields
        (field (name "OCTOPART") "https://octopart.com/cpf0603b430re1-te+connectivity-22738753")
        (field (name "MANUFACTURER PART NUMBER") "CPF0603B430RE1")
      )
      (libsource (lib "Altium Content Vault") (part "1029c3af85768c4190bb7ad29bc67b5"))
    )
    (comp (ref "R33")
      (value "33R 0603")
      (footprint "FP-CPF0603-MFG")
      (description "RES SMD 33Ω 0.1% 1/16W 0603")
      (fields
        (field (name "OCTOPART") "https://octopart.com/cpf0603b430re1-te+connectivity-22738753")
        (field (name "MANUFACTURER PART NUMBER") "CPF0603B430RE1")
      )
      (libsource (lib "Altium Content Vault") (part "1029c3af85768c4190bb7ad29bc67b5"))
    )
    (comp (ref "R34")
      (value "10k 0603")
      (footprint "FP-RT0603-MFG")
      (description "RES SMD 10K OHM 0.05% 1/10W 0603")
      (fields
        (field (name "OCTOPART") "https://octopart.com/rt0603wre0710kl-yageo-71396825")
        (field (name "MANUFACTURER") "Yageo")
      )
      (libsource (lib "Altium Content Vault") (part "1029c3af85768c4190bb7ad29bc67b5"))
    )
    (comp (ref "R35")
      (value "49.9R 0603")
      (footprint "FP-RT0603-MFG")
      (description "RES SMD 49.9 OHM 1% 1/10W 0603")
      (fields (field (name "TOLERANCE") "0.01") (field (name "MANUFACTURER") "Yageo"))
      (libsource (lib "Altium Content Vault") (part "1029c3af85768c4190bb7ad29bc67b5"))
    )
    (comp (ref "R37")
      (value "49.9R 0603")
      (footprint "FP-RT0603-MFG")
      (description "RES SMD 49.9 OHM 1% 1/10W 0603")
      (fields (field (name "TOLERANCE") "0.01") (field (name "MANUFACTURER") "Yageo"))
      (libsource (lib "Altium Content Vault") (part "1029c3af85768c4190bb7ad29bc67b5"))
    )
    (comp (ref "R38")
      (value "0R 0603")
      (footprint "FP-HCJ0603-MFG")
      (description "RES 0 OHM JUMPER 1/4W 0603")
      (libsource (lib "Altium Content Vault") (part "1029c3af85768c4190bb7ad29bc67b5"))
    )
    (comp (ref "R39")
      (value "10k 0603")
      (footprint "FP-RT0603-MFG")
      (description "RES SMD 10K OHM 0.05% 1/10W 0603")
      (fields
        (field (name "OCTOPART") "https://octopart.com/rt0603wre0710kl-yageo-71396825")
        (field (name "MANUFACTURER") "Yageo")
      )
      (libsource (lib "Altium Content Vault") (part "1029c3af85768c4190bb7ad29bc67b5"))
    )
    (comp (ref "R40")
      (value "100k 0603")
      (footprint "FP-RT0603-MFG")
      (description "RT0603 100KΩ 0.1W 50 ppm/°C 1.00%")
      (fields
        (field (name "OCTOPART") "https://octopart.com/rt0603fre10100kl-yageo-22252408")
        (field (name "TOLERANCE") "0.01")
      )
      (libsource (lib "Altium Content Vault") (part "1029c3af85768c4190bb7ad29bc67b5"))
    )
    (comp (ref "R41")
      (value "100k 0603")
      (footprint "FP-RT0603-MFG")
      (description "RT0603 100KΩ 0.1W 50 ppm/°C 1.00%")
      (fields
        (field (name "OCTOPART") "https://octopart.com/rt0603fre10100kl-yageo-22252408")
        (field (name "TOLERANCE") "0.01")
      )
      (libsource (lib "Altium Content Vault") (part "1029c3af85768c4190bb7ad29bc67b5"))
    )
    (comp (ref "R42")
      (value "4.7k 0603")
      (footprint "FP-CPF0603-MFG")
      (description "RES SMD 4.7kΩ 0.1% 1/16W 0603")
      (fields (field (name "TOLERANCE") "0.1%") (field (name "MANUFACTURER") "TE Connectivity"))
      (libsource (lib "Altium Content Vault") (part "1029c3af85768c4190bb7ad29bc67b5"))
    )
    (comp (ref "R43")
      (value "4.7k 0603")
      (footprint "FP-CPF0603-MFG")
      (description "RES SMD 4.7kΩ 0.1% 1/16W 0603")
      (fields (field (name "TOLERANCE") "0.1%") (field (name "MANUFACTURER") "TE Connectivity"))
      (libsource (lib "Altium Content Vault") (part "1029c3af85768c4190bb7ad29bc67b5"))
    )
    (comp (ref "R44")
      (value "1k 0603")
      (footprint "FP-TFCR0603-MFG")
      (description "RES Thin Film,  1kΩ, 0.1%, 0.1W, 25ppm/°C, 0603")
      (libsource (lib "Altium Content Vault") (part "1029c3af85768c4190bb7ad29bc67b5"))
    )
    (comp (ref "R45")
      (value "1k 0603")
      (footprint "FP-TFCR0603-MFG")
      (description "RES Thin Film,  1kΩ, 0.1%, 0.1W, 25ppm/°C, 0603")
      (libsource (lib "Altium Content Vault") (part "1029c3af85768c4190bb7ad29bc67b5"))
    )
    (comp (ref "R46")
      (value "4.7k 0603")
      (footprint "FP-CPF0603-MFG")
      (description "RES SMD 4.7kΩ 0.1% 1/16W 0603")
      (fields (field (name "TOLERANCE") "0.1%") (field (name "MANUFACTURER") "TE Connectivity"))
      (libsource (lib "Altium Content Vault") (part "1029c3af85768c4190bb7ad29bc67b5"))
    )
    (comp (ref "R47")
      (value "4.7k 0603")
      (footprint "FP-CPF0603-MFG")
      (description "RES SMD 4.7kΩ 0.1% 1/16W 0603")
      (fields (field (name "TOLERANCE") "0.1%") (field (name "MANUFACTURER") "TE Connectivity"))
      (libsource (lib "Altium Content Vault") (part "1029c3af85768c4190bb7ad29bc67b5"))
    )
    (comp (ref "R48")
      (value "1k 0603")
      (footprint "FP-TFCR0603-MFG")
      (description "RES Thin Film,  1kΩ, 0.1%, 0.1W, 25ppm/°C, 0603")
      (libsource (lib "Altium Content Vault") (part "1029c3af85768c4190bb7ad29bc67b5"))
    )
    (comp (ref "R49")
      (value "1k 0603")
      (footprint "FP-TFCR0603-MFG")
      (description "RES Thin Film,  1kΩ, 0.1%, 0.1W, 25ppm/°C, 0603")
      (libsource (lib "Altium Content Vault") (part "1029c3af85768c4190bb7ad29bc67b5"))
    )
    (comp (ref "R50")
      (value "100R 0603")
      (footprint "FP-MCT0603-MFG")
      (description "RES SMD 100 OHM 1% 1/8W 0603")
      (fields (field (name "TOLERANCE") "1%"))
      (libsource (lib "Altium Content Vault") (part "1029c3af85768c4190bb7ad29bc67b5"))
    )
    (comp (ref "R51")
      (value "100R 0603")
      (footprint "FP-MCT0603-MFG")
      (description "RES SMD 100 OHM 1% 1/8W 0603")
      (fields (field (name "TOLERANCE") "1%"))
      (libsource (lib "Altium Content Vault") (part "1029c3af85768c4190bb7ad29bc67b5"))
    )
    (comp (ref "R52")
      (value "1k 0603")
      (footprint "FP-TFCR0603-MFG")
      (description "RES Thin Film,  1kΩ, 0.1%, 0.1W, 25ppm/°C, 0603")
      (libsource (lib "Altium Content Vault") (part "1029c3af85768c4190bb7ad29bc67b5"))
    )
    (comp (ref "R53")
      (value "1k 0603")
      (footprint "FP-TFCR0603-MFG")
      (description "RES Thin Film,  1kΩ, 0.1%, 0.1W, 25ppm/°C, 0603")
      (libsource (lib "Altium Content Vault") (part "1029c3af85768c4190bb7ad29bc67b5"))
    )
    (comp (ref "R54")
      (value "33R 0603")
      (footprint "FP-CPF0603-MFG")
      (description "RES SMD 33Ω 0.1% 1/16W 0603")
      (fields
        (field (name "OCTOPART") "https://octopart.com/cpf0603b430re1-te+connectivity-22738753")
        (field (name "MANUFACTURER PART NUMBER") "CPF0603B430RE1")
      )
      (libsource (lib "Altium Content Vault") (part "1029c3af85768c4190bb7ad29bc67b5"))
    )
    (comp (ref "R55")
      (value "33R 0603")
      (footprint "FP-CPF0603-MFG")
      (description "RES SMD 33Ω 0.1% 1/16W 0603")
      (fields
        (field (name "OCTOPART") "https://octopart.com/cpf0603b430re1-te+connectivity-22738753")
        (field (name "MANUFACTURER PART NUMBER") "CPF0603B430RE1")
      )
      (libsource (lib "Altium Content Vault") (part "1029c3af85768c4190bb7ad29bc67b5"))
    )
    (comp (ref "R57")
      (value "33R 0603")
      (footprint "FP-CPF0603-MFG")
      (description "RES SMD 33Ω 0.1% 1/16W 0603")
      (fields
        (field (name "OCTOPART") "https://octopart.com/cpf0603b430re1-te+connectivity-22738753")
        (field (name "MANUFACTURER PART NUMBER") "CPF0603B430RE1")
      )
      (libsource (lib "Altium Content Vault") (part "1029c3af85768c4190bb7ad29bc67b5"))
    )
    (comp (ref "R58")
      (value "33R 0603")
      (footprint "FP-CPF0603-MFG")
      (description "RES SMD 33Ω 0.1% 1/16W 0603")
      (fields
        (field (name "OCTOPART") "https://octopart.com/cpf0603b430re1-te+connectivity-22738753")
        (field (name "MANUFACTURER PART NUMBER") "CPF0603B430RE1")
      )
      (libsource (lib "Altium Content Vault") (part "1029c3af85768c4190bb7ad29bc67b5"))
    )
    (comp (ref "R59")
      (value "33R 0603")
      (footprint "FP-CPF0603-MFG")
      (description "RES SMD 33Ω 0.1% 1/16W 0603")
      (fields
        (field (name "OCTOPART") "https://octopart.com/cpf0603b430re1-te+connectivity-22738753")
        (field (name "MANUFACTURER PART NUMBER") "CPF0603B430RE1")
      )
      (libsource (lib "Altium Content Vault") (part "1029c3af85768c4190bb7ad29bc67b5"))
    )
    (comp (ref "R60")
      (value "33R 0603")
      (footprint "FP-CPF0603-MFG")
      (description "RES SMD 33Ω 0.1% 1/16W 0603")
      (fields
        (field (name "OCTOPART") "https://octopart.com/cpf0603b430re1-te+connectivity-22738753")
        (field (name "MANUFACTURER PART NUMBER") "CPF0603B430RE1")
      )
      (libsource (lib "Altium Content Vault") (part "1029c3af85768c4190bb7ad29bc67b5"))
    )
    (comp (ref "R61")
      (value "33R 0603")
      (footprint "FP-CPF0603-MFG")
      (description "RES SMD 33Ω 0.1% 1/16W 0603")
      (fields
        (field (name "OCTOPART") "https://octopart.com/cpf0603b430re1-te+connectivity-22738753")
        (field (name "MANUFACTURER PART NUMBER") "CPF0603B430RE1")
      )
      (libsource (lib "Altium Content Vault") (part "1029c3af85768c4190bb7ad29bc67b5"))
    )
    (comp (ref "R62")
      (value "33R 0603")
      (footprint "FP-CPF0603-MFG")
      (description "RES SMD 33Ω 0.1% 1/16W 0603")
      (fields
        (field (name "OCTOPART") "https://octopart.com/cpf0603b430re1-te+connectivity-22738753")
        (field (name "MANUFACTURER PART NUMBER") "CPF0603B430RE1")
      )
      (libsource (lib "Altium Content Vault") (part "1029c3af85768c4190bb7ad29bc67b5"))
    )
    (comp (ref "R63")
      (value "33R 0603")
      (footprint "FP-CPF0603-MFG")
      (description "RES SMD 33Ω 0.1% 1/16W 0603")
      (fields
        (field (name "OCTOPART") "https://octopart.com/cpf0603b430re1-te+connectivity-22738753")
        (field (name "MANUFACTURER PART NUMBER") "CPF0603B430RE1")
      )
      (libsource (lib "Altium Content Vault") (part "1029c3af85768c4190bb7ad29bc67b5"))
    )
    (comp (ref "R65")
      (value "33R 0603")
      (footprint "FP-CPF0603-MFG")
      (description "RES SMD 33Ω 0.1% 1/16W 0603")
      (fields
        (field (name "OCTOPART") "https://octopart.com/cpf0603b430re1-te+connectivity-22738753")
        (field (name "MANUFACTURER PART NUMBER") "CPF0603B430RE1")
      )
      (libsource (lib "Altium Content Vault") (part "1029c3af85768c4190bb7ad29bc67b5"))
    )
    (comp (ref "R66")
      (value "33R 0603")
      (footprint "FP-CPF0603-MFG")
      (description "RES SMD 33Ω 0.1% 1/16W 0603")
      (fields
        (field (name "OCTOPART") "https://octopart.com/cpf0603b430re1-te+connectivity-22738753")
        (field (name "MANUFACTURER PART NUMBER") "CPF0603B430RE1")
      )
      (libsource (lib "Altium Content Vault") (part "1029c3af85768c4190bb7ad29bc67b5"))
    )
    (comp (ref "R67")
      (value "33R 0603")
      (footprint "FP-CPF0603-MFG")
      (description "RES SMD 33Ω 0.1% 1/16W 0603")
      (fields
        (field (name "OCTOPART") "https://octopart.com/cpf0603b430re1-te+connectivity-22738753")
        (field (name "MANUFACTURER PART NUMBER") "CPF0603B430RE1")
      )
      (libsource (lib "Altium Content Vault") (part "1029c3af85768c4190bb7ad29bc67b5"))
    )
    (comp (ref "R68")
      (value "33R 0603")
      (footprint "FP-CPF0603-MFG")
      (description "RES SMD 33Ω 0.1% 1/16W 0603")
      (fields
        (field (name "OCTOPART") "https://octopart.com/cpf0603b430re1-te+connectivity-22738753")
        (field (name "MANUFACTURER PART NUMBER") "CPF0603B430RE1")
      )
      (libsource (lib "Altium Content Vault") (part "1029c3af85768c4190bb7ad29bc67b5"))
    )
    (comp (ref "R69")
      (value "33R 0603")
      (footprint "FP-CPF0603-MFG")
      (description "RES SMD 33Ω 0.1% 1/16W 0603")
      (fields
        (field (name "OCTOPART") "https://octopart.com/cpf0603b430re1-te+connectivity-22738753")
        (field (name "MANUFACTURER PART NUMBER") "CPF0603B430RE1")
      )
      (libsource (lib "Altium Content Vault") (part "1029c3af85768c4190bb7ad29bc67b5"))
    )
    (comp (ref "R70")
      (value "33R 0603")
      (footprint "FP-CPF0603-MFG")
      (description "RES SMD 33Ω 0.1% 1/16W 0603")
      (fields
        (field (name "OCTOPART") "https://octopart.com/cpf0603b430re1-te+connectivity-22738753")
        (field (name "MANUFACTURER PART NUMBER") "CPF0603B430RE1")
      )
      (libsource (lib "Altium Content Vault") (part "1029c3af85768c4190bb7ad29bc67b5"))
    )
    (comp (ref "R71")
      (value "33R 0603")
      (footprint "FP-CPF0603-MFG")
      (description "RES SMD 33Ω 0.1% 1/16W 0603")
      (fields
        (field (name "OCTOPART") "https://octopart.com/cpf0603b430re1-te+connectivity-22738753")
        (field (name "MANUFACTURER PART NUMBER") "CPF0603B430RE1")
      )
      (libsource (lib "Altium Content Vault") (part "1029c3af85768c4190bb7ad29bc67b5"))
    )
    (comp (ref "R73")
      (value "33R 0603")
      (footprint "FP-CPF0603-MFG")
      (description "RES SMD 33Ω 0.1% 1/16W 0603")
      (fields
        (field (name "OCTOPART") "https://octopart.com/cpf0603b430re1-te+connectivity-22738753")
        (field (name "MANUFACTURER PART NUMBER") "CPF0603B430RE1")
      )
      (libsource (lib "Altium Content Vault") (part "1029c3af85768c4190bb7ad29bc67b5"))
    )
    (comp (ref "R74")
      (value "33R 0603")
      (footprint "FP-CPF0603-MFG")
      (description "RES SMD 33Ω 0.1% 1/16W 0603")
      (fields
        (field (name "OCTOPART") "https://octopart.com/cpf0603b430re1-te+connectivity-22738753")
        (field (name "MANUFACTURER PART NUMBER") "CPF0603B430RE1")
      )
      (libsource (lib "Altium Content Vault") (part "1029c3af85768c4190bb7ad29bc67b5"))
    )
    (comp (ref "T1")
      (value "HHM22137A2")
      (footprint "HHM22137A2")
      (description "RF Directional Coupler General Purpose 0603 (1608 Metric), 6 PC Pad")
      (fields (field (name "MF") "TDK Corporation"))
      (libsource (lib "") (part "HHM22137A2_1"))
    )
    (comp (ref "T2")
      (value "HHM22137A2")
      (footprint "HHM22137A2")
      (description "RF Directional Coupler General Purpose 0603 (1608 Metric), 6 PC Pad")
      (fields (field (name "MF") "TDK Corporation"))
      (libsource (lib "Ebubekir Taşcı") (part "HHM22137A2"))
    )
    (comp (ref "U1")
      (value "RASPBERRY_PI_PICO_2")
      (footprint "RASPBERRY_PI_PICO")
      (fields (field (name "MF") "Raspberry Pi") (field (name "MP") "RASPBERRY PI PICO"))
      (libsource (lib "Ebubekir Taşcı") (part "RASPBERRY_PI_PICO"))
    )
    (comp (ref "U5")
      (value "ADF4351BCPZ")
      (footprint "ADI-CP-32-2_N")
      (description "Wideband Synthesizer with Integrated VCO, CP-32-2, Pb-Free, 490 Tray")
      (libsource (lib "Altium Content Vault") (part "ADI-ADF4351-CP-32-2"))
    )
    (comp (ref "U6")
      (value "ADF4351BCPZ")
      (footprint "ADI-CP-32-2_N")
      (description "Wideband Synthesizer with Integrated VCO, CP-32-2, Pb-Free, 490 Tray")
      (libsource (lib "Altium Content Vault") (part "ADI-ADF4351-CP-32-2"))
    )
    (comp (ref "U7")
      (value "GVA-62+")
      (footprint "DF782_MNC")
      (description "No Description Available")
      (fields (field (name "COPYRIGHT") "Copyright (C) 2026 Ultra Librarian. All rights reserved."))
      (libsource (lib "GVA-63&plus_") (part "GVA-63+"))
    )
    (comp (ref "U8")
      (value "GVA-62+")
      (footprint "DF782_MNC")
      (description "No Description Available")
      (fields (field (name "COPYRIGHT") "Copyright (C) 2026 Ultra Librarian. All rights reserved."))
      (libsource (lib "GVA-63&plus_") (part "GVA-63+"))
    )
    (comp (ref "U9")
      (value "SYM-63LH+")
      (footprint "FP-SYM-30DMHW+-MFG")
      (description "RF Mixer IC Cellular, GPS, ISM, PCS, WCDMA 1MHz ~ 6GHz")
      (libsource (lib "Altium Content Vault") (part "e4c680c813bfe010d3e16421f7b8462"))
    )
    (comp (ref "U10")
      (value "SYM-63LH+")
      (footprint "FP-SYM-30DMHW+-MFG")
      (description "RF Mixer IC Cellular, GPS, ISM, PCS, WCDMA 1MHz ~ 6GHz")
      (libsource (lib "Altium Content Vault") (part "e4c680c813bfe010d3e16421f7b8462"))
    )
    (comp (ref "U11")
      (value "PCM1808PWR")
      (footprint "SOP65P640X120-14N")
      (description "24-bit, 99-dB SNR, 96-kHz stereo ADC with single-ended inputs")
      (fields (field (name "MF") "Texas Instruments"))
      (libsource (lib "Ebubekir Taşcı") (part "PCM1808PWR"))
    )
    (comp (ref "U13")
      (value "OPA2365AIDR")
      (footprint "FP-D0008A-MFG")
      (description "IC OPAMP GP 2 CIRCUIT 8SOIC")
      (libsource (lib "Altium Content Vault") (part "9ca2bc73342ca7483af30a08cc44e28"))
    )
    (comp (ref "U14")
      (value "OPA2365AIDR")
      (footprint "FP-D0008A-MFG")
      (description "IC OPAMP GP 2 CIRCUIT 8SOIC")
      (libsource (lib "Altium Content Vault") (part "9ca2bc73342ca7483af30a08cc44e28"))
    )
    (comp (ref "U15")
      (value "GVA-62+")
      (footprint "DF782_MNC")
      (description "No Description Available")
      (fields (field (name "COPYRIGHT") "Copyright (C) 2026 Ultra Librarian. All rights reserved."))
      (libsource (lib "GVA-63&plus_") (part "GVA-63+"))
    )
    (comp (ref "U17")
      (value "SI8641BB-B-IS1")
      (footprint "SOIC127P600X265-16N")
      (fields (field (name "MF") "Silicon Labs"))
      (libsource (lib "Ebubekir Taşcı") (part "SI8641BB-B-IS1"))
    )
    (comp (ref "U18")
      (value "SI8641BB-B-IS1")
      (footprint "SOIC127P600X265-16N")
      (fields (field (name "MF") "Silicon Labs"))
      (libsource (lib "Ebubekir Taşcı") (part "SI8641BB-B-IS1"))
    )
    (comp (ref "U19")
      (value "SI8641BB-B-IS1")
      (footprint "SOIC127P600X265-16N")
      (fields (field (name "MF") "Silicon Labs"))
      (libsource (lib "Ebubekir Taşcı") (part "SI8641BB-B-IS1"))
    )
    (comp (ref "Y1")
      (value "ECS-TXO-3225MV-320-TR")
      (footprint "OSC_ECS-TXO-3225MV-320-TR")
      (description "TCXO Oscillators 32.000 MHZ Multi-Volt +1.7 3.6V HCMOS TCXO +/-2.5 ppm -30 +85 C 3.2x 2.5mm RoHS")
      (fields (field (name "MF") "ECS"))
      (libsource (lib "Ebubekir Taşcı") (part "ECS-TXO-3225MV-320-TR"))
    )
  )
  (nets
    (net (code "1") (name "/3V3_Analog") (class "Default")
      (node (ref "C12") (pin "2") (pinfunction "2_2") (pintype "passive"))
      (node (ref "C61") (pin "2") (pinfunction "2_2") (pintype "passive"))
      (node (ref "C62") (pin "2") (pinfunction "2_2") (pintype "passive"))
      (node (ref "R39") (pin "1") (pinfunction "1_1") (pintype "passive"))
      (node (ref "U13") (pin "8") (pinfunction "V+_8") (pintype "power_in"))
      (node (ref "U14") (pin "8") (pinfunction "V+_8") (pintype "power_in"))
      (node (ref "Y1") (pin "1") (pinfunction "TRI-STATE_1") (pintype "input"))
      (node (ref "Y1") (pin "4") (pinfunction "VDD_4") (pintype "input"))
    )
    (net (code "2") (name "/3V3_Digital") (class "Default")
      (node (ref "C51") (pin "2") (pinfunction "2_2") (pintype "passive"))
      (node (ref "U11") (pin "4") (pinfunction "VDD_4") (pintype "power_in"))
      (node (ref "U17") (pin "10") (pinfunction "EN2_10") (pintype "input"))
      (node (ref "U17") (pin "16") (pinfunction "VDD2_16") (pintype "power_in"))
      (node (ref "U18") (pin "10") (pinfunction "EN2_10") (pintype "input"))
      (node (ref "U18") (pin "16") (pinfunction "VDD2_16") (pintype "power_in"))
      (node (ref "U19") (pin "10") (pinfunction "EN2_10") (pintype "input"))
      (node (ref "U19") (pin "16") (pinfunction "VDD2_16") (pintype "power_in"))
    )
    (net (code "3") (name "/3V3_Pico") (class "Default")
      (node (ref "C79") (pin "2") (pinfunction "2_2") (pintype "passive"))
      (node (ref "C80") (pin "2") (pinfunction "2_2") (pintype "passive"))
      (node (ref "C81") (pin "2") (pinfunction "2_2") (pintype "passive"))
      (node (ref "U1") (pin "3V3") (pinfunction "3V3_3V3") (pintype "bidirectional"))
      (node (ref "U17") (pin "1") (pinfunction "VDD1_1") (pintype "power_in"))
      (node (ref "U17") (pin "7") (pinfunction "EN1_7") (pintype "input"))
      (node (ref "U18") (pin "1") (pinfunction "VDD1_1") (pintype "power_in"))
      (node (ref "U18") (pin "7") (pinfunction "EN1_7") (pintype "input"))
      (node (ref "U19") (pin "1") (pinfunction "VDD1_1") (pintype "power_in"))
      (node (ref "U19") (pin "7") (pinfunction "EN1_7") (pintype "input"))
    )
    (net (code "4") (name "/3V3_Synth_1") (class "Default")
      (node (ref "C22") (pin "1") (pinfunction "1_1") (pintype "passive"))
      (node (ref "C23") (pin "2") (pinfunction "2_2") (pintype "passive"))
      (node (ref "C24") (pin "2") (pinfunction "2_2") (pintype "passive"))
      (node (ref "C25") (pin "2") (pinfunction "2_2") (pintype "passive"))
      (node (ref "C26") (pin "1") (pinfunction "1_1") (pintype "passive"))
      (node (ref "C27") (pin "1") (pinfunction "1_1") (pintype "passive"))
      (node (ref "C75") (pin "2") (pinfunction "2_2") (pintype "passive"))
      (node (ref "C76") (pin "1") (pinfunction "1_1") (pintype "passive"))
      (node (ref "L1") (pin "2") (pinfunction "2_2") (pintype "passive"))
      (node (ref "L2") (pin "2") (pinfunction "2_2") (pintype "passive"))
      (node (ref "U5") (pin "10") (pinfunction "AVDD_10") (pintype "power_in"))
      (node (ref "U5") (pin "16") (pinfunction "VVCO_16") (pintype "power_in"))
      (node (ref "U5") (pin "17") (pinfunction "VVCO_17") (pintype "power_in"))
      (node (ref "U5") (pin "26") (pinfunction "PDBRF_26") (pintype "input"))
      (node (ref "U5") (pin "28") (pinfunction "DVDD_28") (pintype "power_in"))
      (node (ref "U5") (pin "32") (pinfunction "SDVDD_32") (pintype "power_in"))
      (node (ref "U5") (pin "4") (pinfunction "CE_4") (pintype "input"))
      (node (ref "U5") (pin "6") (pinfunction "VP_6") (pintype "power_in"))
    )
    (net (code "5") (name "/3V3_Synth_2") (class "Default")
      (node (ref "C34") (pin "1") (pinfunction "1_1") (pintype "passive"))
      (node (ref "C35") (pin "2") (pinfunction "2_2") (pintype "passive"))
      (node (ref "C36") (pin "2") (pinfunction "2_2") (pintype "passive"))
      (node (ref "C37") (pin "2") (pinfunction "2_2") (pintype "passive"))
      (node (ref "C38") (pin "1") (pinfunction "1_1") (pintype "passive"))
      (node (ref "C39") (pin "1") (pinfunction "1_1") (pintype "passive"))
      (node (ref "C77") (pin "2") (pinfunction "2_2") (pintype "passive"))
      (node (ref "C78") (pin "1") (pinfunction "1_1") (pintype "passive"))
      (node (ref "L3") (pin "2") (pinfunction "2_2") (pintype "passive"))
      (node (ref "L4") (pin "2") (pinfunction "2_2") (pintype "passive"))
      (node (ref "U6") (pin "10") (pinfunction "AVDD_10") (pintype "power_in"))
      (node (ref "U6") (pin "16") (pinfunction "VVCO_16") (pintype "power_in"))
      (node (ref "U6") (pin "17") (pinfunction "VVCO_17") (pintype "power_in"))
      (node (ref "U6") (pin "26") (pinfunction "PDBRF_26") (pintype "input"))
      (node (ref "U6") (pin "28") (pinfunction "DVDD_28") (pintype "power_in"))
      (node (ref "U6") (pin "32") (pinfunction "SDVDD_32") (pintype "power_in"))
      (node (ref "U6") (pin "4") (pinfunction "CE_4") (pintype "input"))
      (node (ref "U6") (pin "6") (pinfunction "VP_6") (pintype "power_in"))
    )
    (net (code "6") (name "/4V5") (class "Default")
      (node (ref "C59") (pin "2") (pinfunction "2_2") (pintype "passive"))
      (node (ref "U11") (pin "3") (pinfunction "VCC_3") (pintype "power_in"))
    )
    (net (code "7") (name "/5V_CLN") (class "Default")
      (node (ref "C40") (pin "2") (pinfunction "2_2") (pintype "passive"))
      (node (ref "C41") (pin "2") (pinfunction "2_2") (pintype "passive"))
      (node (ref "C43") (pin "2") (pinfunction "2_2") (pintype "passive"))
      (node (ref "C44") (pin "2") (pinfunction "2_2") (pintype "passive"))
      (node (ref "C55") (pin "2") (pinfunction "2_2") (pintype "passive"))
      (node (ref "C56") (pin "2") (pinfunction "2_2") (pintype "passive"))
      (node (ref "R20") (pin "2") (pinfunction "2_2") (pintype "passive"))
      (node (ref "R24") (pin "2") (pinfunction "2_2") (pintype "passive"))
      (node (ref "R38") (pin "2") (pinfunction "2_2") (pintype "passive"))
    )
    (net (code "8") (name "/BCK") (class "Default")
      (node (ref "R59") (pin "1") (pinfunction "1_1") (pintype "passive"))
      (node (ref "U11") (pin "8") (pinfunction "BCK_8") (pintype "bidirectional"))
    )
    (net (code "9") (name "/BCK_P") (class "Default")
      (node (ref "R61") (pin "2") (pinfunction "2_2") (pintype "passive"))
      (node (ref "U1") (pin "GP19") (pinfunction "GP19_GP19") (pintype "bidirectional"))
    )
    (net (code "10") (name "/CLK_1") (class "Default")
      (node (ref "R32") (pin "1") (pinfunction "1_1") (pintype "passive"))
      (node (ref "U5") (pin "1") (pinfunction "CLK_1") (pintype "input"))
    )
    (net (code "11") (name "/CLK_1_P") (class "Default")
      (node (ref "R55") (pin "2") (pinfunction "2_2") (pintype "passive"))
      (node (ref "U1") (pin "GP2") (pinfunction "GP2_GP2") (pintype "bidirectional"))
    )
    (net (code "12") (name "/CLK_2") (class "Default")
      (node (ref "R68") (pin "1") (pinfunction "1_1") (pintype "passive"))
      (node (ref "U6") (pin "1") (pinfunction "CLK_1") (pintype "input"))
    )
    (net (code "13") (name "/CLK_2_P") (class "Default")
      (node (ref "R71") (pin "2") (pinfunction "2_2") (pintype "passive"))
      (node (ref "U1") (pin "GP10") (pinfunction "GP10_GP10") (pintype "bidirectional"))
    )
    (net (code "14") (name "/CPOUT_1") (class "Default")
      (node (ref "C16") (pin "1") (pinfunction "1_1") (pintype "passive"))
      (node (ref "R11") (pin "2") (pinfunction "2_2") (pintype "passive"))
      (node (ref "R28") (pin "1") (pinfunction "1_1") (pintype "passive"))
      (node (ref "U5") (pin "7") (pinfunction "CPOUT_7") (pintype "output"))
    )
    (net (code "15") (name "/CPOUT_2") (class "Default")
      (node (ref "C32") (pin "1") (pinfunction "1_1") (pintype "passive"))
      (node (ref "R18") (pin "2") (pinfunction "2_2") (pintype "passive"))
      (node (ref "R29") (pin "1") (pinfunction "1_1") (pintype "passive"))
      (node (ref "U6") (pin "7") (pinfunction "CPOUT_7") (pintype "output"))
    )
    (net (code "16") (name "/DATA_1") (class "Default")
      (node (ref "R54") (pin "1") (pinfunction "1_1") (pintype "passive"))
      (node (ref "U5") (pin "2") (pinfunction "DATA_2") (pintype "input"))
    )
    (net (code "17") (name "/DATA_1_P") (class "Default")
      (node (ref "R57") (pin "2") (pinfunction "2_2") (pintype "passive"))
      (node (ref "U1") (pin "GP3") (pinfunction "GP3_GP3") (pintype "bidirectional"))
    )
    (net (code "18") (name "/DATA_2") (class "Default")
      (node (ref "R70") (pin "1") (pinfunction "1_1") (pintype "passive"))
      (node (ref "U6") (pin "2") (pinfunction "DATA_2") (pintype "input"))
    )
    (net (code "19") (name "/DATA_2_P") (class "Default")
      (node (ref "R73") (pin "2") (pinfunction "2_2") (pintype "passive"))
      (node (ref "U1") (pin "GP11") (pinfunction "GP11_GP11") (pintype "bidirectional"))
    )
    (net (code "20") (name "/DOUT") (class "Default")
      (node (ref "R10") (pin "1") (pinfunction "1_1") (pintype "passive"))
      (node (ref "U18") (pin "11") (pinfunction "B4_11") (pintype "bidirectional"))
    )
    (net (code "21") (name "/DOUT_P") (class "Default")
      (node (ref "R66") (pin "2") (pinfunction "2_2") (pintype "passive"))
      (node (ref "U1") (pin "GP22") (pinfunction "GP22_GP22") (pintype "bidirectional"))
    )
    (net (code "22") (name "/FWD_IF") (class "Default")
      (node (ref "C50") (pin "1") (pinfunction "1_1") (pintype "passive"))
      (node (ref "FB6") (pin "1") (pinfunction "1_1") (pintype "passive"))
    )
    (net (code "23") (name "/Forward_Signal") (class "Default")
      (node (ref "C48") (pin "2") (pinfunction "2_2") (pintype "passive"))
      (node (ref "T2") (pin "4") (pinfunction "COUP_4") (pintype "bidirectional"))
    )
    (net (code "24") (name "/LE_1") (class "Default")
      (node (ref "R19") (pin "1") (pinfunction "1_1") (pintype "passive"))
      (node (ref "U5") (pin "3") (pinfunction "LE_3") (pintype "input"))
    )
    (net (code "25") (name "/LE_1_P") (class "Default")
      (node (ref "R33") (pin "2") (pinfunction "2_2") (pintype "passive"))
      (node (ref "U1") (pin "GP1") (pinfunction "GP1_GP1") (pintype "bidirectional"))
    )
    (net (code "26") (name "/LE_2") (class "Default")
      (node (ref "R67") (pin "1") (pinfunction "1_1") (pintype "passive"))
      (node (ref "U6") (pin "3") (pinfunction "LE_3") (pintype "input"))
    )
    (net (code "27") (name "/LE_2_P") (class "Default")
      (node (ref "R69") (pin "2") (pinfunction "2_2") (pintype "passive"))
      (node (ref "U1") (pin "GP9") (pinfunction "GP9_GP9") (pintype "bidirectional"))
    )
    (net (code "28") (name "/LO_1") (class "Default")
      (node (ref "C45") (pin "2") (pinfunction "2_2") (pintype "passive"))
      (node (ref "U9") (pin "2") (pinfunction "LO_2") (pintype "passive"))
    )
    (net (code "29") (name "/LO_2") (class "Default")
      (node (ref "C42") (pin "2") (pinfunction "2_2") (pintype "passive"))
      (node (ref "U10") (pin "2") (pinfunction "LO_2") (pintype "passive"))
    )
    (net (code "30") (name "/LO_OUT") (class "Default")
      (node (ref "C14") (pin "2") (pinfunction "2_2") (pintype "passive"))
      (node (ref "R22") (pin "1") (pinfunction "1_1") (pintype "passive"))
      (node (ref "R52") (pin "2") (pinfunction "2_2") (pintype "passive"))
    )
    (net (code "31") (name "/LRCK") (class "Default")
      (node (ref "R60") (pin "1") (pinfunction "1_1") (pintype "passive"))
      (node (ref "U11") (pin "7") (pinfunction "LRCK_7") (pintype "bidirectional"))
    )
    (net (code "32") (name "/LRCK_P") (class "Default")
      (node (ref "R63") (pin "2") (pinfunction "2_2") (pintype "passive"))
      (node (ref "U1") (pin "GP20") (pinfunction "GP20_GP20") (pintype "bidirectional"))
    )
    (net (code "33") (name "/MUX_1") (class "Default")
      (node (ref "R6") (pin "1") (pinfunction "1_1") (pintype "passive"))
      (node (ref "U17") (pin "11") (pinfunction "B4_11") (pintype "bidirectional"))
    )
    (net (code "34") (name "/MUX_1_P") (class "Default")
      (node (ref "R58") (pin "2") (pinfunction "2_2") (pintype "passive"))
      (node (ref "U1") (pin "GP4") (pinfunction "GP4_GP4") (pintype "bidirectional"))
    )
    (net (code "35") (name "/MUX_2") (class "Default")
      (node (ref "R8") (pin "1") (pinfunction "1_1") (pintype "passive"))
      (node (ref "U19") (pin "11") (pinfunction "B4_11") (pintype "bidirectional"))
    )
    (net (code "36") (name "/MUX_2_P") (class "Default")
      (node (ref "R74") (pin "2") (pinfunction "2_2") (pintype "passive"))
      (node (ref "U1") (pin "GP12") (pinfunction "GP12_GP12") (pintype "bidirectional"))
    )
    (net (code "37") (name "/REFL_IF") (class "Default")
      (node (ref "C54") (pin "1") (pinfunction "1_1") (pintype "passive"))
      (node (ref "FB7") (pin "1") (pinfunction "1_1") (pintype "passive"))
    )
    (net (code "38") (name "/REF_1") (class "Default")
      (node (ref "C4") (pin "1") (pinfunction "1_1") (pintype "passive"))
      (node (ref "R15") (pin "2") (pinfunction "2_2") (pintype "passive"))
    )
    (net (code "39") (name "/REF_2") (class "Default")
      (node (ref "C19") (pin "1") (pinfunction "1_1") (pintype "passive"))
      (node (ref "R4") (pin "2") (pinfunction "2_2") (pintype "passive"))
    )
    (net (code "40") (name "/Reflected_Signal") (class "Default")
      (node (ref "C49") (pin "2") (pinfunction "2_2") (pintype "passive"))
      (node (ref "T1") (pin "4") (pinfunction "COUP_4") (pintype "bidirectional"))
    )
    (net (code "41") (name "/SCKI") (class "Default")
      (node (ref "R62") (pin "1") (pinfunction "1_1") (pintype "passive"))
      (node (ref "U11") (pin "6") (pinfunction "SCKI_6") (pintype "input"))
    )
    (net (code "42") (name "/SCKI_P") (class "Default")
      (node (ref "R65") (pin "2") (pinfunction "2_2") (pintype "passive"))
      (node (ref "U1") (pin "GP21") (pinfunction "GP21_GP21") (pintype "bidirectional"))
    )
    (net (code "43") (name "/Stimulus_OUT") (class "Default")
      (node (ref "R25") (pin "2") (pinfunction "2_2") (pintype "passive"))
      (node (ref "R26") (pin "2") (pinfunction "2_2") (pintype "passive"))
      (node (ref "T2") (pin "3") (pinfunction "INPUT_3") (pintype "bidirectional"))
    )
    (net (code "44") (name "/VINL") (class "Default")
      (node (ref "C68") (pin "1") (pinfunction "1_1") (pintype "passive"))
      (node (ref "R50") (pin "2") (pinfunction "2_2") (pintype "passive"))
      (node (ref "U11") (pin "13") (pinfunction "VINL_13") (pintype "input"))
    )
    (net (code "45") (name "/VINR") (class "Default")
      (node (ref "C70") (pin "1") (pinfunction "1_1") (pintype "passive"))
      (node (ref "R51") (pin "2") (pinfunction "2_2") (pintype "passive"))
      (node (ref "U11") (pin "14") (pinfunction "VINR_14") (pintype "input"))
    )
    (net (code "46") (name "/VTUNE_1") (class "Default")
      (node (ref "C17") (pin "2") (pinfunction "2_2") (pintype "passive"))
      (node (ref "R28") (pin "2") (pinfunction "2_2") (pintype "passive"))
      (node (ref "U5") (pin "20") (pinfunction "VTUNE_20") (pintype "input"))
    )
    (net (code "47") (name "/VTUNE_2") (class "Default")
      (node (ref "C33") (pin "2") (pinfunction "2_2") (pintype "passive"))
      (node (ref "R29") (pin "2") (pinfunction "2_2") (pintype "passive"))
      (node (ref "U6") (pin "20") (pinfunction "VTUNE_20") (pintype "input"))
    )
    (net (code "48") (name "/V_REF") (class "Default")
      (node (ref "C60") (pin "2") (pinfunction "2_2") (pintype "passive"))
      (node (ref "R34") (pin "1") (pinfunction "1_1") (pintype "passive"))
      (node (ref "R39") (pin "2") (pinfunction "2_2") (pintype "passive"))
      (node (ref "R40") (pin "1") (pinfunction "1_1") (pintype "passive"))
      (node (ref "R41") (pin "1") (pinfunction "1_1") (pintype "passive"))
    )
    (net (code "49") (name "GND") (class "Default")
      (node (ref "C12") (pin "1") (pinfunction "1_1") (pintype "passive"))
      (node (ref "C13") (pin "2") (pinfunction "2_2") (pintype "passive"))
      (node (ref "C16") (pin "2") (pinfunction "2_2") (pintype "passive"))
      (node (ref "C17") (pin "1") (pinfunction "1_1") (pintype "passive"))
      (node (ref "C18") (pin "2") (pinfunction "2_2") (pintype "passive"))
      (node (ref "C21") (pin "2") (pinfunction "2_2") (pintype "passive"))
      (node (ref "C22") (pin "2") (pinfunction "2_2") (pintype "passive"))
      (node (ref "C23") (pin "1") (pinfunction "1_1") (pintype "passive"))
      (node (ref "C24") (pin "1") (pinfunction "1_1") (pintype "passive"))
      (node (ref "C25") (pin "1") (pinfunction "1_1") (pintype "passive"))
      (node (ref "C26") (pin "2") (pinfunction "2_2") (pintype "passive"))
      (node (ref "C27") (pin "2") (pinfunction "2_2") (pintype "passive"))
      (node (ref "C29") (pin "2") (pinfunction "2_2") (pintype "passive"))
      (node (ref "C30") (pin "2") (pinfunction "2_2") (pintype "passive"))
      (node (ref "C31") (pin "2") (pinfunction "2_2") (pintype "passive"))
      (node (ref "C32") (pin "2") (pinfunction "2_2") (pintype "passive"))
      (node (ref "C33") (pin "1") (pinfunction "1_1") (pintype "passive"))
      (node (ref "C34") (pin "2") (pinfunction "2_2") (pintype "passive"))
      (node (ref "C35") (pin "1") (pinfunction "1_1") (pintype "passive"))
      (node (ref "C36") (pin "1") (pinfunction "1_1") (pintype "passive"))
      (node (ref "C37") (pin "1") (pinfunction "1_1") (pintype "passive"))
      (node (ref "C38") (pin "2") (pinfunction "2_2") (pintype "passive"))
      (node (ref "C39") (pin "2") (pinfunction "2_2") (pintype "passive"))
      (node (ref "C40") (pin "1") (pinfunction "1_1") (pintype "passive"))
      (node (ref "C41") (pin "1") (pinfunction "1_1") (pintype "passive"))
      (node (ref "C43") (pin "1") (pinfunction "1_1") (pintype "passive"))
      (node (ref "C44") (pin "1") (pinfunction "1_1") (pintype "passive"))
      (node (ref "C46") (pin "1") (pinfunction "1_1") (pintype "passive"))
      (node (ref "C47") (pin "1") (pinfunction "1_1") (pintype "passive"))
      (node (ref "C51") (pin "1") (pinfunction "1_1") (pintype "passive"))
      (node (ref "C52") (pin "1") (pinfunction "1_1") (pintype "passive"))
      (node (ref "C53") (pin "1") (pinfunction "1_1") (pintype "passive"))
      (node (ref "C55") (pin "1") (pinfunction "1_1") (pintype "passive"))
      (node (ref "C56") (pin "1") (pinfunction "1_1") (pintype "passive"))
      (node (ref "C59") (pin "1") (pinfunction "1_1") (pintype "passive"))
      (node (ref "C60") (pin "1") (pinfunction "1_1") (pintype "passive"))
      (node (ref "C61") (pin "1") (pinfunction "1_1") (pintype "passive"))
      (node (ref "C62") (pin "1") (pinfunction "1_1") (pintype "passive"))
      (node (ref "C63") (pin "1") (pinfunction "1_1") (pintype "passive"))
      (node (ref "C64") (pin "1") (pinfunction "1_1") (pintype "passive"))
      (node (ref "C65") (pin "1") (pinfunction "1_1") (pintype "passive"))
      (node (ref "C66") (pin "1") (pinfunction "1_1") (pintype "passive"))
      (node (ref "C68") (pin "2") (pinfunction "2_2") (pintype "passive"))
      (node (ref "C70") (pin "2") (pinfunction "2_2") (pintype "passive"))
      (node (ref "C75") (pin "1") (pinfunction "1_1") (pintype "passive"))
      (node (ref "C76") (pin "2") (pinfunction "2_2") (pintype "passive"))
      (node (ref "C77") (pin "1") (pinfunction "1_1") (pintype "passive"))
      (node (ref "C78") (pin "2") (pinfunction "2_2") (pintype "passive"))
      (node (ref "H1") (pin "1") (pinfunction "SHIELD_1") (pintype "power_in"))
      (node (ref "H1") (pin "10") (pinfunction "SHIELD_10") (pintype "power_in"))
      (node (ref "H1") (pin "11") (pinfunction "SHIELD_11") (pintype "power_in"))
      (node (ref "H1") (pin "12") (pinfunction "SHIELD_12") (pintype "power_in"))
      (node (ref "H1") (pin "13") (pinfunction "SHIELD_13") (pintype "power_in"))
      (node (ref "H1") (pin "14") (pinfunction "SHIELD_14") (pintype "power_in"))
      (node (ref "H1") (pin "15") (pinfunction "SHIELD_15") (pintype "power_in"))
      (node (ref "H1") (pin "16") (pinfunction "SHIELD_16") (pintype "power_in"))
      (node (ref "H1") (pin "17") (pinfunction "SHIELD_17") (pintype "power_in"))
      (node (ref "H1") (pin "18") (pinfunction "SHIELD_18") (pintype "power_in"))
      (node (ref "H1") (pin "19") (pinfunction "SHIELD_19") (pintype "power_in"))
      (node (ref "H1") (pin "2") (pinfunction "SHIELD_2") (pintype "power_in"))
      (node (ref "H1") (pin "20") (pinfunction "SHIELD_20") (pintype "power_in"))
      (node (ref "H1") (pin "21") (pinfunction "SHIELD_21") (pintype "power_in"))
      (node (ref "H1") (pin "22") (pinfunction "SHIELD_22") (pintype "power_in"))
      (node (ref "H1") (pin "23") (pinfunction "SHIELD_23") (pintype "power_in"))
      (node (ref "H1") (pin "24") (pinfunction "SHIELD_24") (pintype "power_in"))
      (node (ref "H1") (pin "3") (pinfunction "SHIELD_3") (pintype "power_in"))
      (node (ref "H1") (pin "4") (pinfunction "SHIELD_4") (pintype "power_in"))
      (node (ref "H1") (pin "5") (pinfunction "SHIELD_5") (pintype "power_in"))
      (node (ref "H1") (pin "6") (pinfunction "SHIELD_6") (pintype "power_in"))
      (node (ref "H1") (pin "7") (pinfunction "SHIELD_7") (pintype "power_in"))
      (node (ref "H1") (pin "8") (pinfunction "SHIELD_8") (pintype "power_in"))
      (node (ref "H1") (pin "9") (pinfunction "SHIELD_9") (pintype "power_in"))
      (node (ref "H2") (pin "1") (pinfunction "SHIELD_1") (pintype "power_in"))
      (node (ref "H2") (pin "10") (pinfunction "SHIELD_10") (pintype "power_in"))
      (node (ref "H2") (pin "11") (pinfunction "SHIELD_11") (pintype "power_in"))
      (node (ref "H2") (pin "12") (pinfunction "SHIELD_12") (pintype "power_in"))
      (node (ref "H2") (pin "13") (pinfunction "SHIELD_13") (pintype "power_in"))
      (node (ref "H2") (pin "14") (pinfunction "SHIELD_14") (pintype "power_in"))
      (node (ref "H2") (pin "15") (pinfunction "SHIELD_15") (pintype "power_in"))
      (node (ref "H2") (pin "16") (pinfunction "SHIELD_16") (pintype "power_in"))
      (node (ref "H2") (pin "17") (pinfunction "SHIELD_17") (pintype "power_in"))
      (node (ref "H2") (pin "18") (pinfunction "SHIELD_18") (pintype "power_in"))
      (node (ref "H2") (pin "19") (pinfunction "SHIELD_19") (pintype "power_in"))
      (node (ref "H2") (pin "2") (pinfunction "SHIELD_2") (pintype "power_in"))
      (node (ref "H2") (pin "20") (pinfunction "SHIELD_20") (pintype "power_in"))
      (node (ref "H2") (pin "21") (pinfunction "SHIELD_21") (pintype "power_in"))
      (node (ref "H2") (pin "22") (pinfunction "SHIELD_22") (pintype "power_in"))
      (node (ref "H2") (pin "23") (pinfunction "SHIELD_23") (pintype "power_in"))
      (node (ref "H2") (pin "24") (pinfunction "SHIELD_24") (pintype "power_in"))
      (node (ref "H2") (pin "3") (pinfunction "SHIELD_3") (pintype "power_in"))
      (node (ref "H2") (pin "4") (pinfunction "SHIELD_4") (pintype "power_in"))
      (node (ref "H2") (pin "5") (pinfunction "SHIELD_5") (pintype "power_in"))
      (node (ref "H2") (pin "6") (pinfunction "SHIELD_6") (pintype "power_in"))
      (node (ref "H2") (pin "7") (pinfunction "SHIELD_7") (pintype "power_in"))
      (node (ref "H2") (pin "8") (pinfunction "SHIELD_8") (pintype "power_in"))
      (node (ref "H2") (pin "9") (pinfunction "SHIELD_9") (pintype "power_in"))
      (node (ref "H3") (pin "1") (pinfunction "SHIELD_1") (pintype "power_in"))
      (node (ref "H3") (pin "10") (pinfunction "SHIELD_10") (pintype "power_in"))
      (node (ref "H3") (pin "11") (pinfunction "SHIELD_11") (pintype "power_in"))
      (node (ref "H3") (pin "12") (pinfunction "SHIELD_12") (pintype "power_in"))
      (node (ref "H3") (pin "13") (pinfunction "SHIELD_13") (pintype "power_in"))
      (node (ref "H3") (pin "14") (pinfunction "SHIELD_14") (pintype "power_in"))
      (node (ref "H3") (pin "15") (pinfunction "SHIELD_15") (pintype "power_in"))
      (node (ref "H3") (pin "16") (pinfunction "SHIELD_16") (pintype "power_in"))
      (node (ref "H3") (pin "17") (pinfunction "SHIELD_17") (pintype "power_in"))
      (node (ref "H3") (pin "18") (pinfunction "SHIELD_18") (pintype "power_in"))
      (node (ref "H3") (pin "19") (pinfunction "SHIELD_19") (pintype "power_in"))
      (node (ref "H3") (pin "2") (pinfunction "SHIELD_2") (pintype "power_in"))
      (node (ref "H3") (pin "20") (pinfunction "SHIELD_20") (pintype "power_in"))
      (node (ref "H3") (pin "21") (pinfunction "SHIELD_21") (pintype "power_in"))
      (node (ref "H3") (pin "22") (pinfunction "SHIELD_22") (pintype "power_in"))
      (node (ref "H3") (pin "23") (pinfunction "SHIELD_23") (pintype "power_in"))
      (node (ref "H3") (pin "24") (pinfunction "SHIELD_24") (pintype "power_in"))
      (node (ref "H3") (pin "3") (pinfunction "SHIELD_3") (pintype "power_in"))
      (node (ref "H3") (pin "4") (pinfunction "SHIELD_4") (pintype "power_in"))
      (node (ref "H3") (pin "5") (pinfunction "SHIELD_5") (pintype "power_in"))
      (node (ref "H3") (pin "6") (pinfunction "SHIELD_6") (pintype "power_in"))
      (node (ref "H3") (pin "7") (pinfunction "SHIELD_7") (pintype "power_in"))
      (node (ref "H3") (pin "8") (pinfunction "SHIELD_8") (pintype "power_in"))
      (node (ref "H3") (pin "9") (pinfunction "SHIELD_9") (pintype "power_in"))
      (node (ref "J1") (pin "2") (pinfunction "MNT_1_2") (pintype "passive"))
      (node (ref "J1") (pin "3") (pinfunction "MNT_2_3") (pintype "passive"))
      (node (ref "J1") (pin "4") (pinfunction "MNT_3_4") (pintype "passive"))
      (node (ref "J1") (pin "5") (pinfunction "MNT_4_5") (pintype "passive"))
      (node (ref "J4") (pin "2") (pinfunction "GND_2") (pintype "power_in"))
      (node (ref "J4") (pin "3") (pinfunction "GND_3") (pintype "power_in"))
      (node (ref "J5") (pin "2") (pinfunction "GND_2") (pintype "power_in"))
      (node (ref "J5") (pin "3") (pinfunction "GND_3") (pintype "power_in"))
      (node (ref "R12") (pin "1") (pinfunction "1_1") (pintype "passive"))
      (node (ref "R14") (pin "1") (pinfunction "1_1") (pintype "passive"))
      (node (ref "R26") (pin "1") (pinfunction "1_1") (pintype "passive"))
      (node (ref "R27") (pin "1") (pinfunction "1_1") (pintype "passive"))
      (node (ref "R30") (pin "1") (pinfunction "1_1") (pintype "passive"))
      (node (ref "R31") (pin "1") (pinfunction "1_1") (pintype "passive"))
      (node (ref "R34") (pin "2") (pinfunction "2_2") (pintype "passive"))
      (node (ref "R35") (pin "1") (pinfunction "1_1") (pintype "passive"))
      (node (ref "R37") (pin "1") (pinfunction "1_1") (pintype "passive"))
      (node (ref "R5") (pin "1") (pinfunction "1_1") (pintype "passive"))
      (node (ref "R7") (pin "1") (pinfunction "1_1") (pintype "passive"))
      (node (ref "T1") (pin "2") (pinfunction "GND_2") (pintype "bidirectional"))
      (node (ref "T1") (pin "5") (pinfunction "GND_5") (pintype "bidirectional"))
      (node (ref "T2") (pin "2") (pinfunction "GND_2") (pintype "bidirectional"))
      (node (ref "T2") (pin "5") (pinfunction "GND_5") (pintype "bidirectional"))
      (node (ref "U10") (pin "4") (pinfunction "GND_4") (pintype "power_in"))
      (node (ref "U10") (pin "5") (pinfunction "GND_5") (pintype "power_in"))
      (node (ref "U10") (pin "6") (pinfunction "GND_6") (pintype "power_in"))
      (node (ref "U11") (pin "10") (pinfunction "MD0_10") (pintype "input"))
      (node (ref "U11") (pin "11") (pinfunction "MD1_11") (pintype "input"))
      (node (ref "U11") (pin "12") (pinfunction "FMT_12") (pintype "input"))
      (node (ref "U11") (pin "2") (pinfunction "AGND_2") (pintype "power_in"))
      (node (ref "U11") (pin "5") (pinfunction "DGND_5") (pintype "power_in"))
      (node (ref "U13") (pin "4") (pinfunction "V-_4") (pintype "power_in"))
      (node (ref "U14") (pin "4") (pinfunction "V-_4") (pintype "power_in"))
      (node (ref "U15") (pin "2") (pinfunction "GROUND_2") (pintype "power_in"))
      (node (ref "U17") (pin "15") (pinfunction "GND2_15") (pintype "power_in"))
      (node (ref "U17") (pin "9") (pinfunction "GND2_9") (pintype "power_in"))
      (node (ref "U18") (pin "15") (pinfunction "GND2_15") (pintype "power_in"))
      (node (ref "U18") (pin "9") (pinfunction "GND2_9") (pintype "power_in"))
      (node (ref "U19") (pin "15") (pinfunction "GND2_15") (pintype "power_in"))
      (node (ref "U19") (pin "9") (pinfunction "GND2_9") (pintype "power_in"))
      (node (ref "U5") (pin "11") (pinfunction "AGNDVCO_11") (pintype "power_in"))
      (node (ref "U5") (pin "18") (pinfunction "AGNDVCO_18") (pintype "power_in"))
      (node (ref "U5") (pin "21") (pinfunction "AGNDVCO_21") (pintype "power_in"))
      (node (ref "U5") (pin "27") (pinfunction "DGND_27") (pintype "power_in"))
      (node (ref "U5") (pin "31") (pinfunction "SDGND_31") (pintype "power_in"))
      (node (ref "U5") (pin "33") (pinfunction "EP_33") (pintype "power_in"))
      (node (ref "U5") (pin "8") (pinfunction "CPGND_8") (pintype "power_in"))
      (node (ref "U5") (pin "9") (pinfunction "AGND_9") (pintype "power_in"))
      (node (ref "U6") (pin "11") (pinfunction "AGNDVCO_11") (pintype "power_in"))
      (node (ref "U6") (pin "18") (pinfunction "AGNDVCO_18") (pintype "power_in"))
      (node (ref "U6") (pin "21") (pinfunction "AGNDVCO_21") (pintype "power_in"))
      (node (ref "U6") (pin "27") (pinfunction "DGND_27") (pintype "power_in"))
      (node (ref "U6") (pin "31") (pinfunction "SDGND_31") (pintype "power_in"))
      (node (ref "U6") (pin "33") (pinfunction "EP_33") (pintype "power_in"))
      (node (ref "U6") (pin "8") (pinfunction "CPGND_8") (pintype "power_in"))
      (node (ref "U6") (pin "9") (pinfunction "AGND_9") (pintype "power_in"))
      (node (ref "U7") (pin "2") (pinfunction "GROUND_2") (pintype "power_in"))
      (node (ref "U8") (pin "2") (pinfunction "GROUND_2") (pintype "power_in"))
      (node (ref "U9") (pin "4") (pinfunction "GND_4") (pintype "power_in"))
      (node (ref "U9") (pin "5") (pinfunction "GND_5") (pintype "power_in"))
      (node (ref "U9") (pin "6") (pinfunction "GND_6") (pintype "power_in"))
      (node (ref "Y1") (pin "2") (pinfunction "GND_2") (pintype "power_in"))
    )
    (net (code "50") (name "Net-(C15-Pad2)") (class "Default")
      (node (ref "C15") (pin "2") (pinfunction "2_2") (pintype "passive"))
      (node (ref "R7") (pin "2") (pinfunction "2_2") (pintype "passive"))
    )
    (net (code "51") (name "Net-(C20-Pad2)") (class "Default")
      (node (ref "C20") (pin "2") (pinfunction "2_2") (pintype "passive"))
      (node (ref "C84") (pin "1") (pinfunction "1_1") (pintype "passive"))
      (node (ref "R53") (pin "2") (pinfunction "2_2") (pintype "passive"))
    )
    (net (code "52") (name "Net-(C28-Pad2)") (class "Default")
      (node (ref "C28") (pin "2") (pinfunction "2_2") (pintype "passive"))
      (node (ref "R12") (pin "2") (pinfunction "2_2") (pintype "passive"))
    )
    (net (code "53") (name "Net-(C46-Pad2)") (class "Default")
      (node (ref "C46") (pin "2") (pinfunction "2_2") (pintype "passive"))
      (node (ref "R11") (pin "1") (pinfunction "1_1") (pintype "passive"))
    )
    (net (code "54") (name "Net-(C47-Pad2)") (class "Default")
      (node (ref "C47") (pin "2") (pinfunction "2_2") (pintype "passive"))
      (node (ref "R18") (pin "1") (pinfunction "1_1") (pintype "passive"))
    )
    (net (code "55") (name "Net-(C63-Pad2)") (class "Default")
      (node (ref "C63") (pin "2") (pinfunction "2_2") (pintype "passive"))
      (node (ref "R44") (pin "1") (pinfunction "1_1") (pintype "passive"))
    )
    (net (code "56") (name "Net-(C64-Pad2)") (class "Default")
      (node (ref "C64") (pin "2") (pinfunction "2_2") (pintype "passive"))
      (node (ref "R45") (pin "1") (pinfunction "1_1") (pintype "passive"))
    )
    (net (code "57") (name "Net-(C65-Pad2)") (class "Default")
      (node (ref "C65") (pin "2") (pinfunction "2_2") (pintype "passive"))
      (node (ref "R48") (pin "1") (pinfunction "1_1") (pintype "passive"))
    )
    (net (code "58") (name "Net-(C66-Pad2)") (class "Default")
      (node (ref "C66") (pin "2") (pinfunction "2_2") (pintype "passive"))
      (node (ref "R49") (pin "1") (pinfunction "1_1") (pintype "passive"))
    )
    (net (code "59") (name "Net-(C67-Pad2)") (class "Default")
      (node (ref "C67") (pin "2") (pinfunction "2_2") (pintype "passive"))
      (node (ref "R50") (pin "1") (pinfunction "1_1") (pintype "passive"))
    )
    (net (code "60") (name "Net-(C69-Pad2)") (class "Default")
      (node (ref "C69") (pin "2") (pinfunction "2_2") (pintype "passive"))
      (node (ref "R51") (pin "1") (pinfunction "1_1") (pintype "passive"))
    )
    (net (code "61") (name "Net-(C71-Pad2)") (class "Default")
      (node (ref "C71") (pin "2") (pinfunction "2_2") (pintype "passive"))
      (node (ref "R25") (pin "1") (pinfunction "1_1") (pintype "passive"))
      (node (ref "R27") (pin "2") (pinfunction "2_2") (pintype "passive"))
    )
    (net (code "62") (name "Net-(C72-Pad2)") (class "Default")
      (node (ref "C72") (pin "2") (pinfunction "2_2") (pintype "passive"))
      (node (ref "J1") (pin "1") (pinfunction "1_1") (pintype "passive"))
    )
    (net (code "63") (name "Net-(C82-Pad2)") (class "Default")
      (node (ref "C82") (pin "2") (pinfunction "2_2") (pintype "passive"))
      (node (ref "R21") (pin "2") (pinfunction "2_2") (pintype "passive"))
    )
    (net (code "64") (name "Net-(C83-Pad1)") (class "Default")
      (node (ref "C83") (pin "1") (pinfunction "1_1") (pintype "passive"))
      (node (ref "R23") (pin "1") (pinfunction "1_1") (pintype "passive"))
    )
    (net (code "65") (name "Net-(J4-Pad1)") (class "Default")
      (node (ref "J4") (pin "1") (pinfunction "1_1") (pintype "passive"))
      (node (ref "R52") (pin "1") (pinfunction "1_1") (pintype "passive"))
    )
    (net (code "66") (name "Net-(J5-Pad1)") (class "Default")
      (node (ref "J5") (pin "1") (pinfunction "1_1") (pintype "passive"))
      (node (ref "R53") (pin "1") (pinfunction "1_1") (pintype "passive"))
    )
    (net (code "67") (name "Net-(L5-Pad2)") (class "Default")
      (node (ref "L5") (pin "2") (pinfunction "2_2") (pintype "passive"))
      (node (ref "R20") (pin "1") (pinfunction "1_1") (pintype "passive"))
    )
    (net (code "68") (name "Net-(L6-Pad2)") (class "Default")
      (node (ref "L6") (pin "2") (pinfunction "2_2") (pintype "passive"))
      (node (ref "R24") (pin "1") (pinfunction "1_1") (pintype "passive"))
    )
    (net (code "69") (name "Net-(L7-Pad2)") (class "Default")
      (node (ref "L7") (pin "2") (pinfunction "2_2") (pintype "passive"))
      (node (ref "R38") (pin "1") (pinfunction "1_1") (pintype "passive"))
    )
    (net (code "70") (name "Net-(R21-Pad1)") (class "Default")
      (node (ref "R21") (pin "1") (pinfunction "1_1") (pintype "passive"))
      (node (ref "R22") (pin "2") (pinfunction "2_2") (pintype "passive"))
      (node (ref "R23") (pin "2") (pinfunction "2_2") (pintype "passive"))
    )
    (net (code "71") (name "Net-(T1-DIRECT)") (class "Default")
      (node (ref "T1") (pin "1") (pinfunction "DIRECT_1") (pintype "bidirectional"))
      (node (ref "T2") (pin "1") (pinfunction "DIRECT_1") (pintype "bidirectional"))
    )
    (net (code "72") (name "Net-(T1-INPUT)") (class "Default")
      (node (ref "C72") (pin "1") (pinfunction "1_1") (pintype "passive"))
      (node (ref "T1") (pin "3") (pinfunction "INPUT_3") (pintype "bidirectional"))
    )
    (net (code "73") (name "Net-(T1-ISOL)") (class "Default")
      (node (ref "R31") (pin "2") (pinfunction "2_2") (pintype "passive"))
      (node (ref "T1") (pin "6") (pinfunction "ISOL_6") (pintype "bidirectional"))
    )
    (net (code "74") (name "Net-(T2-ISOL)") (class "Default")
      (node (ref "R30") (pin "2") (pinfunction "2_2") (pintype "passive"))
      (node (ref "T2") (pin "6") (pinfunction "ISOL_6") (pintype "bidirectional"))
    )
    (net (code "75") (name "Net-(U5-MUXOUT)") (class "Default")
      (node (ref "R6") (pin "2") (pinfunction "2_2") (pintype "passive"))
      (node (ref "U5") (pin "30") (pinfunction "MUXOUT_30") (pintype "output"))
    )
    (net (code "76") (name "Net-(U5-REFIN)") (class "Default")
      (node (ref "C4") (pin "2") (pinfunction "2_2") (pintype "passive"))
      (node (ref "U5") (pin "29") (pinfunction "REFIN_29") (pintype "input"))
    )
    (net (code "77") (name "Net-(U5-RFOUTA+)") (class "Default")
      (node (ref "C14") (pin "1") (pinfunction "1_1") (pintype "passive"))
      (node (ref "L2") (pin "1") (pinfunction "1_1") (pintype "passive"))
      (node (ref "U5") (pin "12") (pinfunction "RFOUTA+_12") (pintype "output"))
    )
    (net (code "78") (name "Net-(U5-RFOUTA-)") (class "Default")
      (node (ref "C15") (pin "1") (pinfunction "1_1") (pintype "passive"))
      (node (ref "L1") (pin "1") (pinfunction "1_1") (pintype "passive"))
      (node (ref "U5") (pin "13") (pinfunction "RFOUTA-_13") (pintype "output"))
    )
    (net (code "79") (name "Net-(U5-RSET)") (class "Default")
      (node (ref "R5") (pin "2") (pinfunction "2_2") (pintype "passive"))
      (node (ref "U5") (pin "22") (pinfunction "RSET_22") (pintype "input"))
    )
    (net (code "80") (name "Net-(U5-TEMP)") (class "Default")
      (node (ref "C13") (pin "1") (pinfunction "1_1") (pintype "passive"))
      (node (ref "U5") (pin "19") (pinfunction "TEMP_19") (pintype "passive"))
    )
    (net (code "81") (name "Net-(U5-VCOM)") (class "Default")
      (node (ref "C21") (pin "1") (pinfunction "1_1") (pintype "passive"))
      (node (ref "U5") (pin "23") (pinfunction "VCOM_23") (pintype "passive"))
    )
    (net (code "82") (name "Net-(U5-VREF)") (class "Default")
      (node (ref "C18") (pin "1") (pinfunction "1_1") (pintype "passive"))
      (node (ref "U5") (pin "24") (pinfunction "VREF_24") (pintype "passive"))
    )
    (net (code "83") (name "Net-(U6-MUXOUT)") (class "Default")
      (node (ref "R8") (pin "2") (pinfunction "2_2") (pintype "passive"))
      (node (ref "U6") (pin "30") (pinfunction "MUXOUT_30") (pintype "output"))
    )
    (net (code "84") (name "Net-(U6-REFIN)") (class "Default")
      (node (ref "C19") (pin "2") (pinfunction "2_2") (pintype "passive"))
      (node (ref "U6") (pin "29") (pinfunction "REFIN_29") (pintype "input"))
    )
    (net (code "85") (name "Net-(U6-RFOUTA+)") (class "Default")
      (node (ref "C20") (pin "1") (pinfunction "1_1") (pintype "passive"))
      (node (ref "L4") (pin "1") (pinfunction "1_1") (pintype "passive"))
      (node (ref "U6") (pin "12") (pinfunction "RFOUTA+_12") (pintype "output"))
    )
    (net (code "86") (name "Net-(U6-RFOUTA-)") (class "Default")
      (node (ref "C28") (pin "1") (pinfunction "1_1") (pintype "passive"))
      (node (ref "L3") (pin "1") (pinfunction "1_1") (pintype "passive"))
      (node (ref "U6") (pin "13") (pinfunction "RFOUTA-_13") (pintype "output"))
    )
    (net (code "87") (name "Net-(U6-RSET)") (class "Default")
      (node (ref "R14") (pin "2") (pinfunction "2_2") (pintype "passive"))
      (node (ref "U6") (pin "22") (pinfunction "RSET_22") (pintype "input"))
    )
    (net (code "88") (name "Net-(U6-TEMP)") (class "Default")
      (node (ref "C29") (pin "1") (pinfunction "1_1") (pintype "passive"))
      (node (ref "U6") (pin "19") (pinfunction "TEMP_19") (pintype "passive"))
    )
    (net (code "89") (name "Net-(U6-VCOM)") (class "Default")
      (node (ref "C31") (pin "1") (pinfunction "1_1") (pintype "passive"))
      (node (ref "U6") (pin "23") (pinfunction "VCOM_23") (pintype "passive"))
    )
    (net (code "90") (name "Net-(U6-VREF)") (class "Default")
      (node (ref "C30") (pin "1") (pinfunction "1_1") (pintype "passive"))
      (node (ref "U6") (pin "24") (pinfunction "VREF_24") (pintype "passive"))
    )
    (net (code "91") (name "Net-(U7-RF-IN)") (class "Default")
      (node (ref "C82") (pin "1") (pinfunction "1_1") (pintype "passive"))
      (node (ref "U7") (pin "1") (pinfunction "RF-IN_1") (pintype "input"))
    )
    (net (code "92") (name "Net-(U7-RF-OUT{slash}DC-IN)") (class "Default")
      (node (ref "C42") (pin "1") (pinfunction "1_1") (pintype "passive"))
      (node (ref "L5") (pin "1") (pinfunction "1_1") (pintype "passive"))
      (node (ref "U7") (pin "3") (pinfunction "RF-OUT/DC-IN_3") (pintype "passive"))
    )
    (net (code "93") (name "Net-(U8-RF-IN)") (class "Default")
      (node (ref "C83") (pin "2") (pinfunction "2_2") (pintype "passive"))
      (node (ref "U8") (pin "1") (pinfunction "RF-IN_1") (pintype "input"))
    )
    (net (code "94") (name "Net-(U8-RF-OUT{slash}DC-IN)") (class "Default")
      (node (ref "C45") (pin "1") (pinfunction "1_1") (pintype "passive"))
      (node (ref "L6") (pin "1") (pinfunction "1_1") (pintype "passive"))
      (node (ref "U8") (pin "3") (pinfunction "RF-OUT/DC-IN_3") (pintype "passive"))
    )
    (net (code "95") (name "Net-(U9-IF)") (class "Default")
      (node (ref "FB6") (pin "2") (pinfunction "2_2") (pintype "passive"))
      (node (ref "R35") (pin "2") (pinfunction "2_2") (pintype "passive"))
      (node (ref "U9") (pin "3") (pinfunction "IF_3") (pintype "passive"))
    )
    (net (code "96") (name "Net-(U9-RF)") (class "Default")
      (node (ref "C48") (pin "1") (pinfunction "1_1") (pintype "passive"))
      (node (ref "U9") (pin "1") (pinfunction "RF_1") (pintype "passive"))
    )
    (net (code "97") (name "Net-(U10-IF)") (class "Default")
      (node (ref "FB7") (pin "2") (pinfunction "2_2") (pintype "passive"))
      (node (ref "R37") (pin "2") (pinfunction "2_2") (pintype "passive"))
      (node (ref "U10") (pin "3") (pinfunction "IF_3") (pintype "passive"))
    )
    (net (code "98") (name "Net-(U10-RF)") (class "Default")
      (node (ref "C49") (pin "1") (pinfunction "1_1") (pintype "passive"))
      (node (ref "U10") (pin "1") (pinfunction "RF_1") (pintype "passive"))
    )
    (net (code "99") (name "Net-(U11-DOUT)") (class "Default")
      (node (ref "R10") (pin "2") (pinfunction "2_2") (pintype "passive"))
      (node (ref "U11") (pin "9") (pinfunction "DOUT_9") (pintype "output"))
    )
    (net (code "100") (name "Net-(U11-VREF)") (class "Default")
      (node (ref "C52") (pin "2") (pinfunction "2_2") (pintype "passive"))
      (node (ref "C53") (pin "2") (pinfunction "2_2") (pintype "passive"))
      (node (ref "U11") (pin "1") (pinfunction "VREF_1") (pintype "input"))
    )
    (net (code "101") (name "Net-(U13A-IN_A+)") (class "Default")
      (node (ref "C50") (pin "2") (pinfunction "2_2") (pintype "passive"))
      (node (ref "R40") (pin "2") (pinfunction "2_2") (pintype "passive"))
      (node (ref "U13") (pin "3") (pinfunction "IN_A+_3") (pintype "tri_state"))
    )
    (net (code "102") (name "Net-(U13A-IN_A-)") (class "Default")
      (node (ref "R42") (pin "2") (pinfunction "2_2") (pintype "passive"))
      (node (ref "R44") (pin "2") (pinfunction "2_2") (pintype "passive"))
      (node (ref "U13") (pin "2") (pinfunction "IN_A-_2") (pintype "tri_state"))
    )
    (net (code "103") (name "Net-(U13A-VOUTA)") (class "Default")
      (node (ref "R42") (pin "1") (pinfunction "1_1") (pintype "passive"))
      (node (ref "U13") (pin "1") (pinfunction "VOUTA_1") (pintype "output"))
      (node (ref "U14") (pin "3") (pinfunction "IN_A+_3") (pintype "tri_state"))
    )
    (net (code "104") (name "Net-(U13B-IN_B+)") (class "Default")
      (node (ref "C54") (pin "2") (pinfunction "2_2") (pintype "passive"))
      (node (ref "R41") (pin "2") (pinfunction "2_2") (pintype "passive"))
      (node (ref "U13") (pin "5") (pinfunction "IN_B+_5") (pintype "tri_state"))
    )
    (net (code "105") (name "Net-(U13B-IN_B-)") (class "Default")
      (node (ref "R46") (pin "2") (pinfunction "2_2") (pintype "passive"))
      (node (ref "R48") (pin "2") (pinfunction "2_2") (pintype "passive"))
      (node (ref "U13") (pin "6") (pinfunction "IN_B-_6") (pintype "tri_state"))
    )
    (net (code "106") (name "Net-(U13B-VOUTB)") (class "Default")
      (node (ref "R46") (pin "1") (pinfunction "1_1") (pintype "passive"))
      (node (ref "U13") (pin "7") (pinfunction "VOUTB_7") (pintype "output"))
      (node (ref "U14") (pin "5") (pinfunction "IN_B+_5") (pintype "tri_state"))
    )
    (net (code "107") (name "Net-(U14A-IN_A-)") (class "Default")
      (node (ref "R43") (pin "2") (pinfunction "2_2") (pintype "passive"))
      (node (ref "R45") (pin "2") (pinfunction "2_2") (pintype "passive"))
      (node (ref "U14") (pin "2") (pinfunction "IN_A-_2") (pintype "tri_state"))
    )
    (net (code "108") (name "Net-(U14A-VOUTA)") (class "Default")
      (node (ref "C67") (pin "1") (pinfunction "1_1") (pintype "passive"))
      (node (ref "R43") (pin "1") (pinfunction "1_1") (pintype "passive"))
      (node (ref "U14") (pin "1") (pinfunction "VOUTA_1") (pintype "output"))
    )
    (net (code "109") (name "Net-(U14B-IN_B-)") (class "Default")
      (node (ref "R47") (pin "2") (pinfunction "2_2") (pintype "passive"))
      (node (ref "R49") (pin "2") (pinfunction "2_2") (pintype "passive"))
      (node (ref "U14") (pin "6") (pinfunction "IN_B-_6") (pintype "tri_state"))
    )
    (net (code "110") (name "Net-(U14B-VOUTB)") (class "Default")
      (node (ref "C69") (pin "1") (pinfunction "1_1") (pintype "passive"))
      (node (ref "R47") (pin "1") (pinfunction "1_1") (pintype "passive"))
      (node (ref "U14") (pin "7") (pinfunction "VOUTB_7") (pintype "output"))
    )
    (net (code "111") (name "Net-(U15-RF-IN)") (class "Default")
      (node (ref "C84") (pin "2") (pinfunction "2_2") (pintype "passive"))
      (node (ref "U15") (pin "1") (pinfunction "RF-IN_1") (pintype "input"))
    )
    (net (code "112") (name "Net-(U15-RF-OUT{slash}DC-IN)") (class "Default")
      (node (ref "C71") (pin "1") (pinfunction "1_1") (pintype "passive"))
      (node (ref "L7") (pin "1") (pinfunction "1_1") (pintype "passive"))
      (node (ref "U15") (pin "3") (pinfunction "RF-OUT/DC-IN_3") (pintype "passive"))
    )
    (net (code "113") (name "Net-(U17-A1)") (class "Default")
      (node (ref "R33") (pin "1") (pinfunction "1_1") (pintype "passive"))
      (node (ref "U17") (pin "3") (pinfunction "A1_3") (pintype "input"))
    )
    (net (code "114") (name "Net-(U17-A2)") (class "Default")
      (node (ref "R55") (pin "1") (pinfunction "1_1") (pintype "passive"))
      (node (ref "U17") (pin "4") (pinfunction "A2_4") (pintype "input"))
    )
    (net (code "115") (name "Net-(U17-A3)") (class "Default")
      (node (ref "R57") (pin "1") (pinfunction "1_1") (pintype "passive"))
      (node (ref "U17") (pin "5") (pinfunction "A3_5") (pintype "bidirectional"))
    )
    (net (code "116") (name "Net-(U17-A4)") (class "Default")
      (node (ref "R58") (pin "1") (pinfunction "1_1") (pintype "passive"))
      (node (ref "U17") (pin "6") (pinfunction "A4_6") (pintype "bidirectional"))
    )
    (net (code "117") (name "Net-(U17-B1)") (class "Default")
      (node (ref "R19") (pin "2") (pinfunction "2_2") (pintype "passive"))
      (node (ref "U17") (pin "14") (pinfunction "B1_14") (pintype "output"))
    )
    (net (code "118") (name "Net-(U17-B2)") (class "Default")
      (node (ref "R32") (pin "2") (pinfunction "2_2") (pintype "passive"))
      (node (ref "U17") (pin "13") (pinfunction "B2_13") (pintype "output"))
    )
    (net (code "119") (name "Net-(U17-B3)") (class "Default")
      (node (ref "R54") (pin "2") (pinfunction "2_2") (pintype "passive"))
      (node (ref "U17") (pin "12") (pinfunction "B3_12") (pintype "bidirectional"))
    )
    (net (code "120") (name "Net-(U18-A1)") (class "Default")
      (node (ref "R61") (pin "1") (pinfunction "1_1") (pintype "passive"))
      (node (ref "U18") (pin "3") (pinfunction "A1_3") (pintype "input"))
    )
    (net (code "121") (name "Net-(U18-A2)") (class "Default")
      (node (ref "R63") (pin "1") (pinfunction "1_1") (pintype "passive"))
      (node (ref "U18") (pin "4") (pinfunction "A2_4") (pintype "input"))
    )
    (net (code "122") (name "Net-(U18-A3)") (class "Default")
      (node (ref "R65") (pin "1") (pinfunction "1_1") (pintype "passive"))
      (node (ref "U18") (pin "5") (pinfunction "A3_5") (pintype "bidirectional"))
    )
    (net (code "123") (name "Net-(U18-A4)") (class "Default")
      (node (ref "R66") (pin "1") (pinfunction "1_1") (pintype "passive"))
      (node (ref "U18") (pin "6") (pinfunction "A4_6") (pintype "bidirectional"))
    )
    (net (code "124") (name "Net-(U18-B1)") (class "Default")
      (node (ref "R59") (pin "2") (pinfunction "2_2") (pintype "passive"))
      (node (ref "U18") (pin "14") (pinfunction "B1_14") (pintype "output"))
    )
    (net (code "125") (name "Net-(U18-B2)") (class "Default")
      (node (ref "R60") (pin "2") (pinfunction "2_2") (pintype "passive"))
      (node (ref "U18") (pin "13") (pinfunction "B2_13") (pintype "output"))
    )
    (net (code "126") (name "Net-(U18-B3)") (class "Default")
      (node (ref "R62") (pin "2") (pinfunction "2_2") (pintype "passive"))
      (node (ref "U18") (pin "12") (pinfunction "B3_12") (pintype "bidirectional"))
    )
    (net (code "127") (name "Net-(U19-A1)") (class "Default")
      (node (ref "R69") (pin "1") (pinfunction "1_1") (pintype "passive"))
      (node (ref "U19") (pin "3") (pinfunction "A1_3") (pintype "input"))
    )
    (net (code "128") (name "Net-(U19-A2)") (class "Default")
      (node (ref "R71") (pin "1") (pinfunction "1_1") (pintype "passive"))
      (node (ref "U19") (pin "4") (pinfunction "A2_4") (pintype "input"))
    )
    (net (code "129") (name "Net-(U19-A3)") (class "Default")
      (node (ref "R73") (pin "1") (pinfunction "1_1") (pintype "passive"))
      (node (ref "U19") (pin "5") (pinfunction "A3_5") (pintype "bidirectional"))
    )
    (net (code "130") (name "Net-(U19-A4)") (class "Default")
      (node (ref "R74") (pin "1") (pinfunction "1_1") (pintype "passive"))
      (node (ref "U19") (pin "6") (pinfunction "A4_6") (pintype "bidirectional"))
    )
    (net (code "131") (name "Net-(U19-B1)") (class "Default")
      (node (ref "R67") (pin "2") (pinfunction "2_2") (pintype "passive"))
      (node (ref "U19") (pin "14") (pinfunction "B1_14") (pintype "output"))
    )
    (net (code "132") (name "Net-(U19-B2)") (class "Default")
      (node (ref "R68") (pin "2") (pinfunction "2_2") (pintype "passive"))
      (node (ref "U19") (pin "13") (pinfunction "B2_13") (pintype "output"))
    )
    (net (code "133") (name "Net-(U19-B3)") (class "Default")
      (node (ref "R70") (pin "2") (pinfunction "2_2") (pintype "passive"))
      (node (ref "U19") (pin "12") (pinfunction "B3_12") (pintype "bidirectional"))
    )
    (net (code "134") (name "Net-(Y1-OUTPUT)") (class "Default")
      (node (ref "R15") (pin "1") (pinfunction "1_1") (pintype "passive"))
      (node (ref "R4") (pin "1") (pinfunction "1_1") (pintype "passive"))
      (node (ref "Y1") (pin "3") (pinfunction "OUTPUT_3") (pintype "output"))
    )
    (net (code "135") (name "PICO_GND") (class "Default")
      (node (ref "C79") (pin "1") (pinfunction "1_1") (pintype "passive"))
      (node (ref "C80") (pin "1") (pinfunction "1_1") (pintype "passive"))
      (node (ref "C81") (pin "1") (pinfunction "1_1") (pintype "passive"))
      (node (ref "U1") (pin "AGND") (pinfunction "AGND_AGND") (pintype "bidirectional"))
      (node (ref "U1") (pin "GND") (pinfunction "GND_GND") (pintype "bidirectional"))
      (node (ref "U1") (pin "GND2") (pinfunction "GND2_GND2") (pintype "bidirectional"))
      (node (ref "U1") (pin "GND3") (pinfunction "GND3_GND3") (pintype "bidirectional"))
      (node (ref "U1") (pin "GND4") (pinfunction "GND4_GND4") (pintype "bidirectional"))
      (node (ref "U1") (pin "GND5") (pinfunction "GND5_GND5") (pintype "bidirectional"))
      (node (ref "U1") (pin "GND6") (pinfunction "GND6_GND6") (pintype "bidirectional"))
      (node (ref "U1") (pin "GND7") (pinfunction "GND7_GND7") (pintype "bidirectional"))
      (node (ref "U17") (pin "2") (pinfunction "GND1_2") (pintype "power_in"))
      (node (ref "U17") (pin "8") (pinfunction "GND1_8") (pintype "power_in"))
      (node (ref "U18") (pin "2") (pinfunction "GND1_2") (pintype "power_in"))
      (node (ref "U18") (pin "8") (pinfunction "GND1_8") (pintype "power_in"))
      (node (ref "U19") (pin "2") (pinfunction "GND1_2") (pintype "power_in"))
      (node (ref "U19") (pin "8") (pinfunction "GND1_8") (pintype "power_in"))
    )
    (net (code "136") (name "unconnected-(U1-Pad3V3_EN)") (class "Default")
      (node (ref "U1") (pin "3V3_EN") (pinfunction "3V3_EN_3V3_EN") (pintype "bidirectional"))
    )
    (net (code "137") (name "unconnected-(U1-PadADC_VREF)") (class "Default")
      (node (ref "U1") (pin "ADC_VREF") (pinfunction "ADC_VREF_ADC_VREF") (pintype "bidirectional"))
    )
    (net (code "138") (name "unconnected-(U1-PadGP0)") (class "Default")
      (node (ref "U1") (pin "GP0") (pinfunction "GP0_GP0") (pintype "bidirectional"))
    )
    (net (code "139") (name "unconnected-(U1-PadGP5)") (class "Default")
      (node (ref "U1") (pin "GP5") (pinfunction "GP5_GP5") (pintype "bidirectional"))
    )
    (net (code "140") (name "unconnected-(U1-PadGP6)") (class "Default")
      (node (ref "U1") (pin "GP6") (pinfunction "GP6_GP6") (pintype "bidirectional"))
    )
    (net (code "141") (name "unconnected-(U1-PadGP7)") (class "Default")
      (node (ref "U1") (pin "GP7") (pinfunction "GP7_GP7") (pintype "bidirectional"))
    )
    (net (code "142") (name "unconnected-(U1-PadGP8)") (class "Default")
      (node (ref "U1") (pin "GP8") (pinfunction "GP8_GP8") (pintype "bidirectional"))
    )
    (net (code "143") (name "unconnected-(U1-PadGP13)") (class "Default")
      (node (ref "U1") (pin "GP13") (pinfunction "GP13_GP13") (pintype "bidirectional"))
    )
    (net (code "144") (name "unconnected-(U1-PadGP14)") (class "Default")
      (node (ref "U1") (pin "GP14") (pinfunction "GP14_GP14") (pintype "bidirectional"))
    )
    (net (code "145") (name "unconnected-(U1-PadGP15)") (class "Default")
      (node (ref "U1") (pin "GP15") (pinfunction "GP15_GP15") (pintype "bidirectional"))
    )
    (net (code "146") (name "unconnected-(U1-PadGP16)") (class "Default")
      (node (ref "U1") (pin "GP16") (pinfunction "GP16_GP16") (pintype "bidirectional"))
    )
    (net (code "147") (name "unconnected-(U1-PadGP17)") (class "Default")
      (node (ref "U1") (pin "GP17") (pinfunction "GP17_GP17") (pintype "bidirectional"))
    )
    (net (code "148") (name "unconnected-(U1-PadGP18)") (class "Default")
      (node (ref "U1") (pin "GP18") (pinfunction "GP18_GP18") (pintype "bidirectional"))
    )
    (net (code "149") (name "unconnected-(U1-PadGP26_A0)") (class "Default")
      (node (ref "U1") (pin "GP26_A0") (pinfunction "GP26_A0_GP26_A0") (pintype "bidirectional"))
    )
    (net (code "150") (name "unconnected-(U1-PadGP27_A1)") (class "Default")
      (node (ref "U1") (pin "GP27_A1") (pinfunction "GP27_A1_GP27_A1") (pintype "bidirectional"))
    )
    (net (code "151") (name "unconnected-(U1-PadGP28_A2)") (class "Default")
      (node (ref "U1") (pin "GP28_A2") (pinfunction "GP28_A2_GP28_A2") (pintype "bidirectional"))
    )
    (net (code "152") (name "unconnected-(U1-PadRUN)") (class "Default")
      (node (ref "U1") (pin "RUN") (pinfunction "RUN_RUN") (pintype "bidirectional+no_connect"))
    )
    (net (code "153") (name "unconnected-(U1-PadVBUS)") (class "Default")
      (node (ref "U1") (pin "VBUS") (pinfunction "VBUS_VBUS") (pintype "bidirectional+no_connect"))
    )
    (net (code "154") (name "unconnected-(U1-PadVSYS)") (class "Default")
      (node (ref "U1") (pin "VSYS") (pinfunction "VSYS_VSYS") (pintype "bidirectional+no_connect"))
    )
    (net (code "155") (name "unconnected-(U5-LD-Pad25)") (class "Default")
      (node (ref "U5") (pin "25") (pinfunction "LD_25") (pintype "output+no_connect"))
    )
    (net (code "156") (name "unconnected-(U5-RFOUTB+-Pad14)") (class "Default")
      (node (ref "U5") (pin "14") (pinfunction "RFOUTB+_14") (pintype "output+no_connect"))
    )
    (net (code "157") (name "unconnected-(U5-RFOUTB--Pad15)") (class "Default")
      (node (ref "U5") (pin "15") (pinfunction "RFOUTB-_15") (pintype "output+no_connect"))
    )
    (net (code "158") (name "unconnected-(U5-SW-Pad5)") (class "Default")
      (node (ref "U5") (pin "5") (pinfunction "SW_5") (pintype "passive+no_connect"))
    )
    (net (code "159") (name "unconnected-(U6-LD-Pad25)") (class "Default")
      (node (ref "U6") (pin "25") (pinfunction "LD_25") (pintype "output+no_connect"))
    )
    (net (code "160") (name "unconnected-(U6-RFOUTB+-Pad14)") (class "Default")
      (node (ref "U6") (pin "14") (pinfunction "RFOUTB+_14") (pintype "output+no_connect"))
    )
    (net (code "161") (name "unconnected-(U6-RFOUTB--Pad15)") (class "Default")
      (node (ref "U6") (pin "15") (pinfunction "RFOUTB-_15") (pintype "output+no_connect"))
    )
    (net (code "162") (name "unconnected-(U6-SW-Pad5)") (class "Default")
      (node (ref "U6") (pin "5") (pinfunction "SW_5") (pintype "passive+no_connect"))
    )
  )
)
